# Adafruit_NeoTrellis_M4.net
KiCad netlist of a schematic drawn in EAGLE
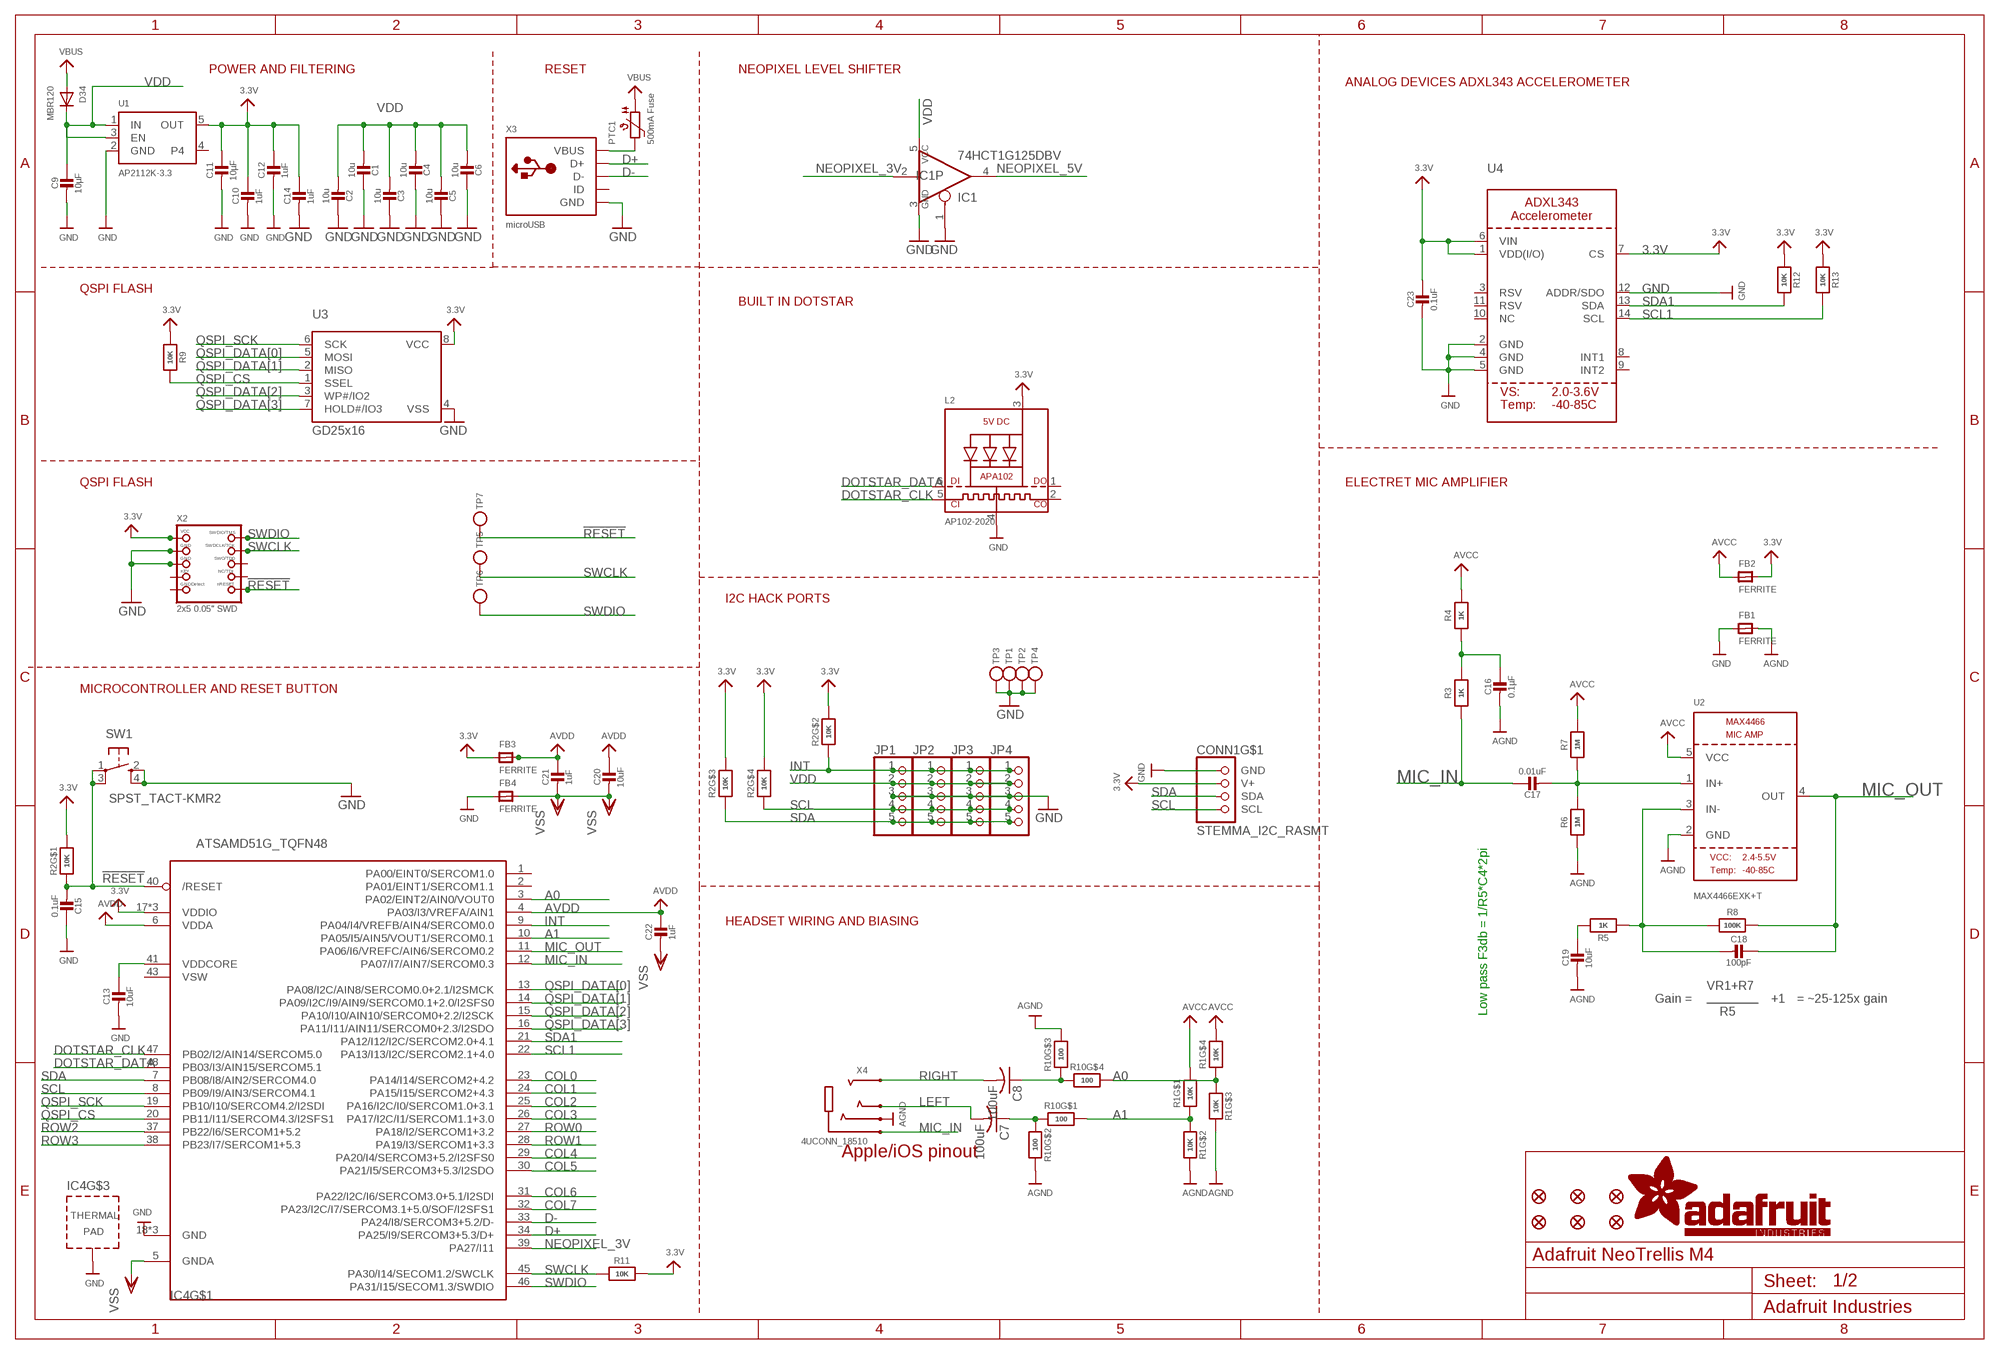
[diagram p0: schematic, sheet 1]
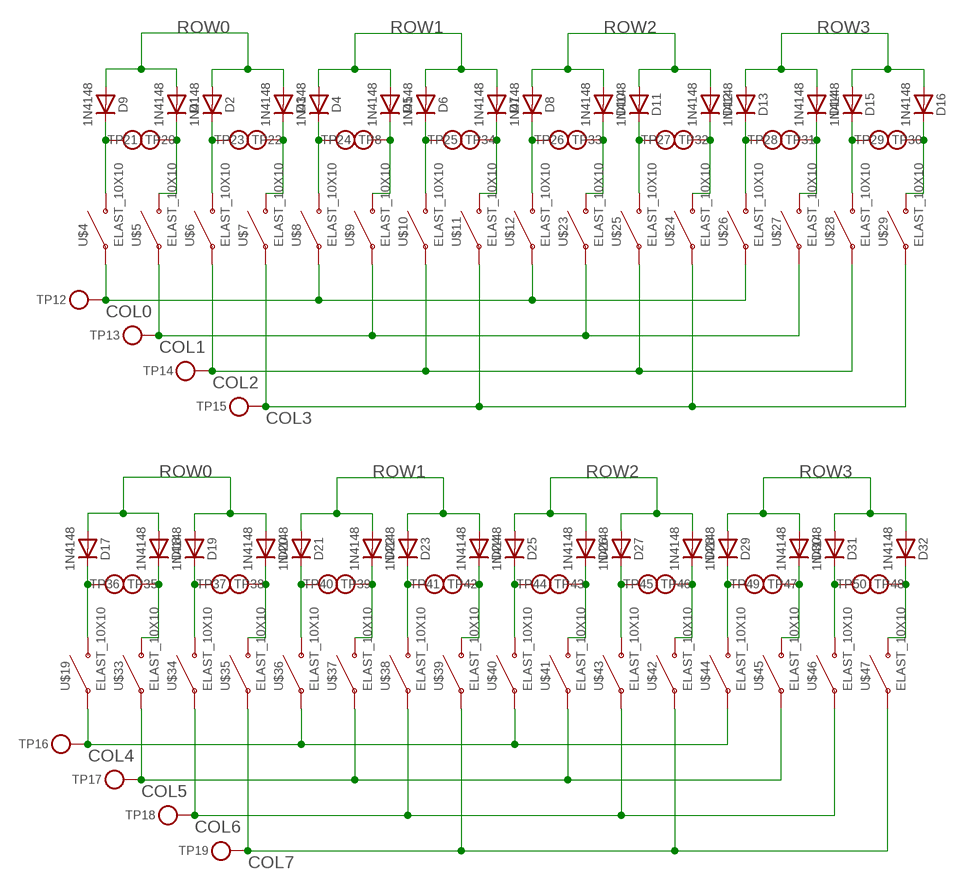
[diagram p1: schematic, sheet 2, part 1 of 2]
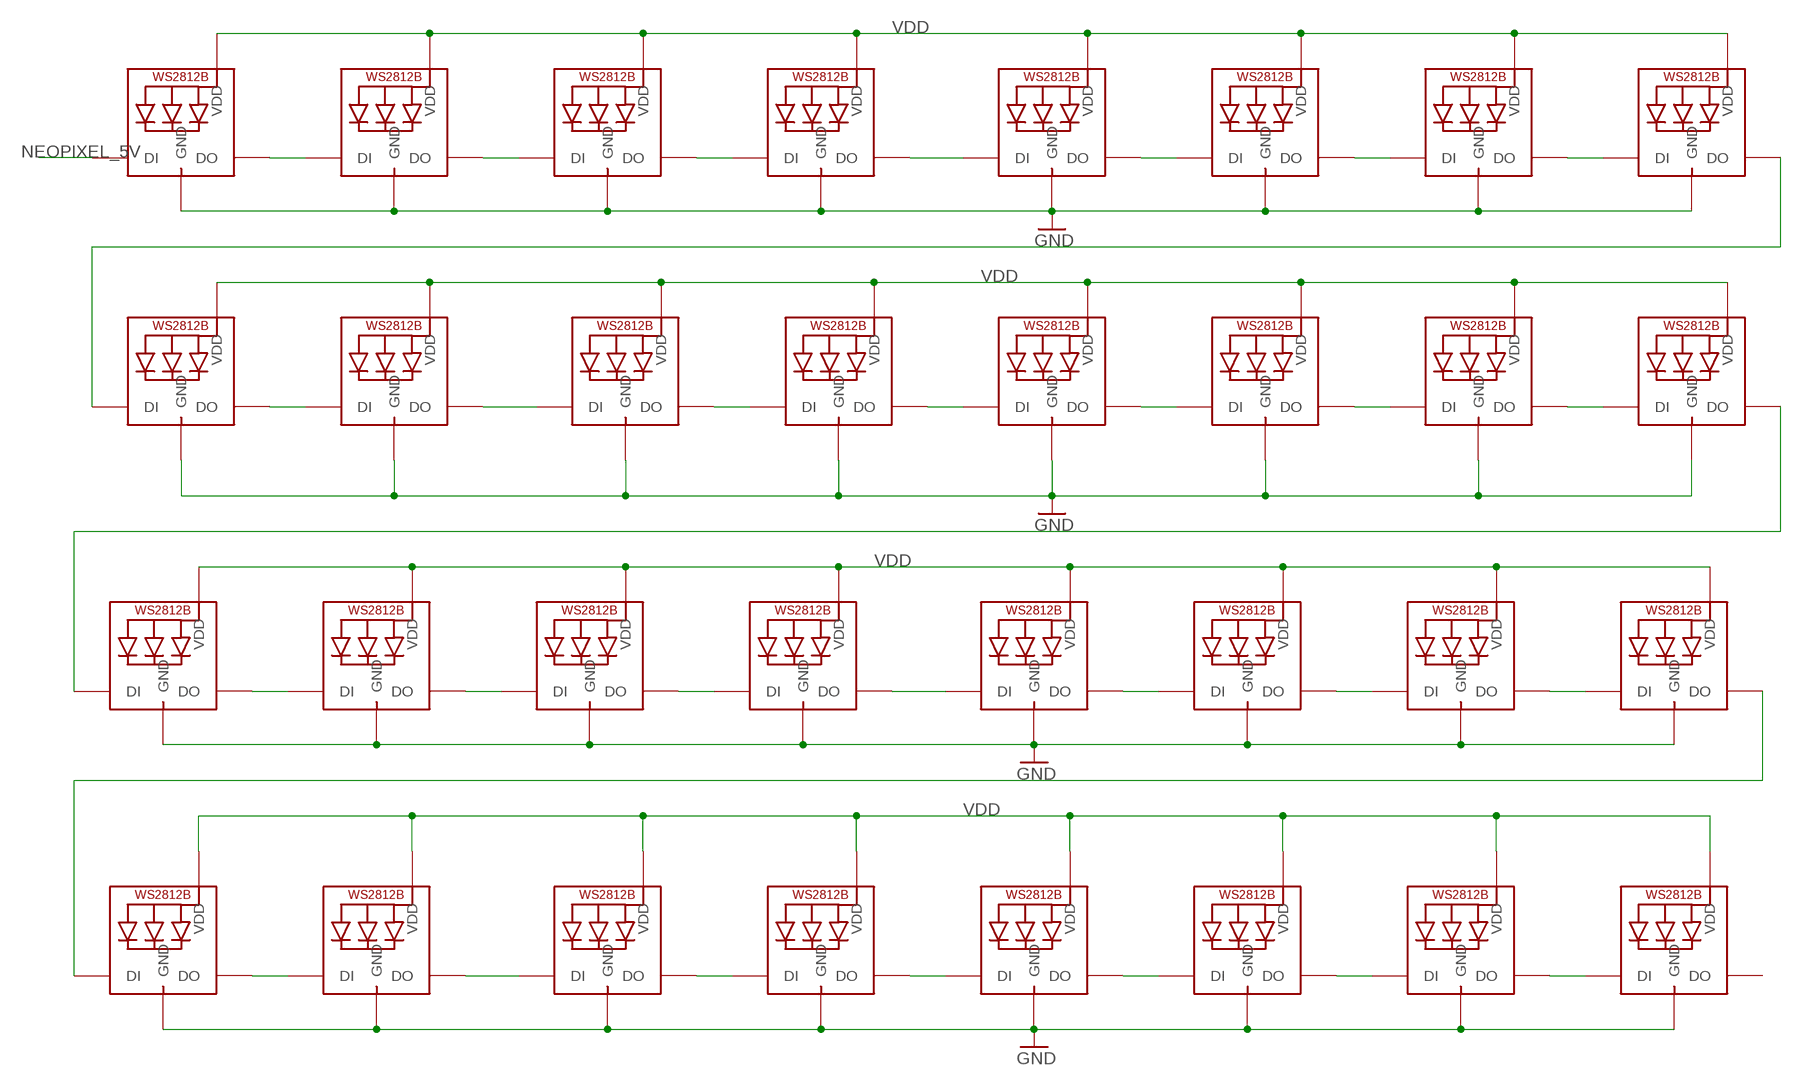
[diagram p2: schematic, sheet 2, part 2 of 2]

(export (version "E")
  (design (tool "Eeschema 10.0.6"))
  (components
    (comp (ref "D1")
      (value "1N4148")
      (footprint "eagle-import:SOD-323")
      (libsource (lib "eagle-import") (part "DIODESOD-323"))
    )
    (comp (ref "D2")
      (value "1N4148")
      (footprint "eagle-import:SOD-323")
      (libsource (lib "eagle-import") (part "DIODESOD-323"))
    )
    (comp (ref "D3")
      (value "1N4148")
      (footprint "eagle-import:SOD-323")
      (libsource (lib "eagle-import") (part "DIODESOD-323"))
    )
    (comp (ref "D4")
      (value "1N4148")
      (footprint "eagle-import:SOD-323")
      (libsource (lib "eagle-import") (part "DIODESOD-323"))
    )
    (comp (ref "D5")
      (value "1N4148")
      (footprint "eagle-import:SOD-323")
      (libsource (lib "eagle-import") (part "DIODESOD-323"))
    )
    (comp (ref "D6")
      (value "1N4148")
      (footprint "eagle-import:SOD-323")
      (libsource (lib "eagle-import") (part "DIODESOD-323"))
    )
    (comp (ref "D7")
      (value "1N4148")
      (footprint "eagle-import:SOD-323")
      (libsource (lib "eagle-import") (part "DIODESOD-323"))
    )
    (comp (ref "D8")
      (value "1N4148")
      (footprint "eagle-import:SOD-323")
      (libsource (lib "eagle-import") (part "DIODESOD-323"))
    )
    (comp (ref "D9")
      (value "1N4148")
      (footprint "eagle-import:SOD-323")
      (libsource (lib "eagle-import") (part "DIODESOD-323"))
    )
    (comp (ref "D10")
      (value "1N4148")
      (footprint "eagle-import:SOD-323")
      (libsource (lib "eagle-import") (part "DIODESOD-323"))
    )
    (comp (ref "D11")
      (value "1N4148")
      (footprint "eagle-import:SOD-323")
      (libsource (lib "eagle-import") (part "DIODESOD-323"))
    )
    (comp (ref "D12")
      (value "1N4148")
      (footprint "eagle-import:SOD-323")
      (libsource (lib "eagle-import") (part "DIODESOD-323"))
    )
    (comp (ref "D13")
      (value "1N4148")
      (footprint "eagle-import:SOD-323")
      (libsource (lib "eagle-import") (part "DIODESOD-323"))
    )
    (comp (ref "D14")
      (value "1N4148")
      (footprint "eagle-import:SOD-323")
      (libsource (lib "eagle-import") (part "DIODESOD-323"))
    )
    (comp (ref "D15")
      (value "1N4148")
      (footprint "eagle-import:SOD-323")
      (libsource (lib "eagle-import") (part "DIODESOD-323"))
    )
    (comp (ref "D16")
      (value "1N4148")
      (footprint "eagle-import:SOD-323")
      (libsource (lib "eagle-import") (part "DIODESOD-323"))
    )
    (comp (ref "D17")
      (value "1N4148")
      (footprint "eagle-import:SOD-323")
      (libsource (lib "eagle-import") (part "DIODESOD-323"))
    )
    (comp (ref "D18")
      (value "1N4148")
      (footprint "eagle-import:SOD-323")
      (libsource (lib "eagle-import") (part "DIODESOD-323"))
    )
    (comp (ref "D19")
      (value "1N4148")
      (footprint "eagle-import:SOD-323")
      (libsource (lib "eagle-import") (part "DIODESOD-323"))
    )
    (comp (ref "D20")
      (value "1N4148")
      (footprint "eagle-import:SOD-323")
      (libsource (lib "eagle-import") (part "DIODESOD-323"))
    )
    (comp (ref "D21")
      (value "1N4148")
      (footprint "eagle-import:SOD-323")
      (libsource (lib "eagle-import") (part "DIODESOD-323"))
    )
    (comp (ref "D22")
      (value "1N4148")
      (footprint "eagle-import:SOD-323")
      (libsource (lib "eagle-import") (part "DIODESOD-323"))
    )
    (comp (ref "D23")
      (value "1N4148")
      (footprint "eagle-import:SOD-323")
      (libsource (lib "eagle-import") (part "DIODESOD-323"))
    )
    (comp (ref "D24")
      (value "1N4148")
      (footprint "eagle-import:SOD-323")
      (libsource (lib "eagle-import") (part "DIODESOD-323"))
    )
    (comp (ref "D25")
      (value "1N4148")
      (footprint "eagle-import:SOD-323")
      (libsource (lib "eagle-import") (part "DIODESOD-323"))
    )
    (comp (ref "D26")
      (value "1N4148")
      (footprint "eagle-import:SOD-323")
      (libsource (lib "eagle-import") (part "DIODESOD-323"))
    )
    (comp (ref "D27")
      (value "1N4148")
      (footprint "eagle-import:SOD-323")
      (libsource (lib "eagle-import") (part "DIODESOD-323"))
    )
    (comp (ref "D28")
      (value "1N4148")
      (footprint "eagle-import:SOD-323")
      (libsource (lib "eagle-import") (part "DIODESOD-323"))
    )
    (comp (ref "D29")
      (value "1N4148")
      (footprint "eagle-import:SOD-323")
      (libsource (lib "eagle-import") (part "DIODESOD-323"))
    )
    (comp (ref "D30")
      (value "1N4148")
      (footprint "eagle-import:SOD-323")
      (libsource (lib "eagle-import") (part "DIODESOD-323"))
    )
    (comp (ref "D31")
      (value "1N4148")
      (footprint "eagle-import:SOD-323")
      (libsource (lib "eagle-import") (part "DIODESOD-323"))
    )
    (comp (ref "D32")
      (value "1N4148")
      (footprint "eagle-import:SOD-323")
      (libsource (lib "eagle-import") (part "DIODESOD-323"))
    )
    (comp (ref "LED1")
      (value "WS2812B3535")
      (footprint "eagle-import:LED3535")
      (libsource (lib "eagle-import") (part "WS2812B3535"))
    )
    (comp (ref "LED2")
      (value "WS2812B3535")
      (footprint "eagle-import:LED3535")
      (libsource (lib "eagle-import") (part "WS2812B3535"))
    )
    (comp (ref "LED3")
      (value "WS2812B3535")
      (footprint "eagle-import:LED3535")
      (libsource (lib "eagle-import") (part "WS2812B3535"))
    )
    (comp (ref "LED4")
      (value "WS2812B3535")
      (footprint "eagle-import:LED3535")
      (libsource (lib "eagle-import") (part "WS2812B3535"))
    )
    (comp (ref "LED5")
      (value "WS2812B3535")
      (footprint "eagle-import:LED3535")
      (libsource (lib "eagle-import") (part "WS2812B3535"))
    )
    (comp (ref "LED6")
      (value "WS2812B3535")
      (footprint "eagle-import:LED3535")
      (libsource (lib "eagle-import") (part "WS2812B3535"))
    )
    (comp (ref "LED7")
      (value "WS2812B3535")
      (footprint "eagle-import:LED3535")
      (libsource (lib "eagle-import") (part "WS2812B3535"))
    )
    (comp (ref "LED8")
      (value "WS2812B3535")
      (footprint "eagle-import:LED3535")
      (libsource (lib "eagle-import") (part "WS2812B3535"))
    )
    (comp (ref "LED9")
      (value "WS2812B3535")
      (footprint "eagle-import:LED3535")
      (libsource (lib "eagle-import") (part "WS2812B3535"))
    )
    (comp (ref "LED10")
      (value "WS2812B3535")
      (footprint "eagle-import:LED3535")
      (libsource (lib "eagle-import") (part "WS2812B3535"))
    )
    (comp (ref "LED11")
      (value "WS2812B3535")
      (footprint "eagle-import:LED3535")
      (libsource (lib "eagle-import") (part "WS2812B3535"))
    )
    (comp (ref "LED12")
      (value "WS2812B3535")
      (footprint "eagle-import:LED3535")
      (libsource (lib "eagle-import") (part "WS2812B3535"))
    )
    (comp (ref "LED13")
      (value "WS2812B3535")
      (footprint "eagle-import:LED3535")
      (libsource (lib "eagle-import") (part "WS2812B3535"))
    )
    (comp (ref "LED14")
      (value "WS2812B3535")
      (footprint "eagle-import:LED3535")
      (libsource (lib "eagle-import") (part "WS2812B3535"))
    )
    (comp (ref "LED15")
      (value "WS2812B3535")
      (footprint "eagle-import:LED3535")
      (libsource (lib "eagle-import") (part "WS2812B3535"))
    )
    (comp (ref "LED16")
      (value "WS2812B3535")
      (footprint "eagle-import:LED3535")
      (libsource (lib "eagle-import") (part "WS2812B3535"))
    )
    (comp (ref "LED17")
      (value "WS2812B3535")
      (footprint "eagle-import:LED3535")
      (libsource (lib "eagle-import") (part "WS2812B3535"))
    )
    (comp (ref "LED18")
      (value "WS2812B3535")
      (footprint "eagle-import:LED3535")
      (libsource (lib "eagle-import") (part "WS2812B3535"))
    )
    (comp (ref "LED19")
      (value "WS2812B3535")
      (footprint "eagle-import:LED3535")
      (libsource (lib "eagle-import") (part "WS2812B3535"))
    )
    (comp (ref "LED20")
      (value "WS2812B3535")
      (footprint "eagle-import:LED3535")
      (libsource (lib "eagle-import") (part "WS2812B3535"))
    )
    (comp (ref "LED21")
      (value "WS2812B3535")
      (footprint "eagle-import:LED3535")
      (libsource (lib "eagle-import") (part "WS2812B3535"))
    )
    (comp (ref "LED22")
      (value "WS2812B3535")
      (footprint "eagle-import:LED3535")
      (libsource (lib "eagle-import") (part "WS2812B3535"))
    )
    (comp (ref "LED23")
      (value "WS2812B3535")
      (footprint "eagle-import:LED3535")
      (libsource (lib "eagle-import") (part "WS2812B3535"))
    )
    (comp (ref "LED24")
      (value "WS2812B3535")
      (footprint "eagle-import:LED3535")
      (libsource (lib "eagle-import") (part "WS2812B3535"))
    )
    (comp (ref "LED25")
      (value "WS2812B3535")
      (footprint "eagle-import:LED3535")
      (libsource (lib "eagle-import") (part "WS2812B3535"))
    )
    (comp (ref "LED26")
      (value "WS2812B3535")
      (footprint "eagle-import:LED3535")
      (libsource (lib "eagle-import") (part "WS2812B3535"))
    )
    (comp (ref "LED27")
      (value "WS2812B3535")
      (footprint "eagle-import:LED3535")
      (libsource (lib "eagle-import") (part "WS2812B3535"))
    )
    (comp (ref "LED28")
      (value "WS2812B3535")
      (footprint "eagle-import:LED3535")
      (libsource (lib "eagle-import") (part "WS2812B3535"))
    )
    (comp (ref "LED29")
      (value "WS2812B3535")
      (footprint "eagle-import:LED3535")
      (libsource (lib "eagle-import") (part "WS2812B3535"))
    )
    (comp (ref "LED30")
      (value "WS2812B3535")
      (footprint "eagle-import:LED3535")
      (libsource (lib "eagle-import") (part "WS2812B3535"))
    )
    (comp (ref "LED31")
      (value "WS2812B3535")
      (footprint "eagle-import:LED3535")
      (libsource (lib "eagle-import") (part "WS2812B3535"))
    )
    (comp (ref "LED32")
      (value "WS2812B3535")
      (footprint "eagle-import:LED3535")
      (libsource (lib "eagle-import") (part "WS2812B3535"))
    )
    (comp (ref "TP8")
      (value "TESTPOINTROUND1.5MM")
      (footprint "eagle-import:TESTPOINT_ROUND_1.5MM")
      (libsource (lib "eagle-import") (part "TESTPOINTROUND1.5MM"))
    )
    (comp (ref "TP12")
      (value "TESTPOINTROUND1.5MM")
      (footprint "eagle-import:TESTPOINT_ROUND_1.5MM")
      (libsource (lib "eagle-import") (part "TESTPOINTROUND1.5MM"))
    )
    (comp (ref "TP13")
      (value "TESTPOINTROUND1.5MM")
      (footprint "eagle-import:TESTPOINT_ROUND_1.5MM")
      (libsource (lib "eagle-import") (part "TESTPOINTROUND1.5MM"))
    )
    (comp (ref "TP14")
      (value "TESTPOINTROUND1.5MM")
      (footprint "eagle-import:TESTPOINT_ROUND_1.5MM")
      (libsource (lib "eagle-import") (part "TESTPOINTROUND1.5MM"))
    )
    (comp (ref "TP15")
      (value "TESTPOINTROUND1.5MM")
      (footprint "eagle-import:TESTPOINT_ROUND_1.5MM")
      (libsource (lib "eagle-import") (part "TESTPOINTROUND1.5MM"))
    )
    (comp (ref "TP16")
      (value "TESTPOINTROUND1.5MM")
      (footprint "eagle-import:TESTPOINT_ROUND_1.5MM")
      (libsource (lib "eagle-import") (part "TESTPOINTROUND1.5MM"))
    )
    (comp (ref "TP17")
      (value "TESTPOINTROUND1.5MM")
      (footprint "eagle-import:TESTPOINT_ROUND_1.5MM")
      (libsource (lib "eagle-import") (part "TESTPOINTROUND1.5MM"))
    )
    (comp (ref "TP18")
      (value "TESTPOINTROUND1.5MM")
      (footprint "eagle-import:TESTPOINT_ROUND_1.5MM")
      (libsource (lib "eagle-import") (part "TESTPOINTROUND1.5MM"))
    )
    (comp (ref "TP19")
      (value "TESTPOINTROUND1.5MM")
      (footprint "eagle-import:TESTPOINT_ROUND_1.5MM")
      (libsource (lib "eagle-import") (part "TESTPOINTROUND1.5MM"))
    )
    (comp (ref "TP20")
      (value "TESTPOINTROUND1.5MM")
      (footprint "eagle-import:TESTPOINT_ROUND_1.5MM")
      (libsource (lib "eagle-import") (part "TESTPOINTROUND1.5MM"))
    )
    (comp (ref "TP21")
      (value "TESTPOINTROUND1.5MM")
      (footprint "eagle-import:TESTPOINT_ROUND_1.5MM")
      (libsource (lib "eagle-import") (part "TESTPOINTROUND1.5MM"))
    )
    (comp (ref "TP22")
      (value "TESTPOINTROUND1.5MM")
      (footprint "eagle-import:TESTPOINT_ROUND_1.5MM")
      (libsource (lib "eagle-import") (part "TESTPOINTROUND1.5MM"))
    )
    (comp (ref "TP23")
      (value "TESTPOINTROUND1.5MM")
      (footprint "eagle-import:TESTPOINT_ROUND_1.5MM")
      (libsource (lib "eagle-import") (part "TESTPOINTROUND1.5MM"))
    )
    (comp (ref "TP24")
      (value "TESTPOINTROUND1.5MM")
      (footprint "eagle-import:TESTPOINT_ROUND_1.5MM")
      (libsource (lib "eagle-import") (part "TESTPOINTROUND1.5MM"))
    )
    (comp (ref "TP25")
      (value "TESTPOINTROUND1.5MM")
      (footprint "eagle-import:TESTPOINT_ROUND_1.5MM")
      (libsource (lib "eagle-import") (part "TESTPOINTROUND1.5MM"))
    )
    (comp (ref "TP26")
      (value "TESTPOINTROUND1.5MM")
      (footprint "eagle-import:TESTPOINT_ROUND_1.5MM")
      (libsource (lib "eagle-import") (part "TESTPOINTROUND1.5MM"))
    )
    (comp (ref "TP27")
      (value "TESTPOINTROUND1.5MM")
      (footprint "eagle-import:TESTPOINT_ROUND_1.5MM")
      (libsource (lib "eagle-import") (part "TESTPOINTROUND1.5MM"))
    )
    (comp (ref "TP28")
      (value "TESTPOINTROUND1.5MM")
      (footprint "eagle-import:TESTPOINT_ROUND_1.5MM")
      (libsource (lib "eagle-import") (part "TESTPOINTROUND1.5MM"))
    )
    (comp (ref "TP29")
      (value "TESTPOINTROUND1.5MM")
      (footprint "eagle-import:TESTPOINT_ROUND_1.5MM")
      (libsource (lib "eagle-import") (part "TESTPOINTROUND1.5MM"))
    )
    (comp (ref "TP30")
      (value "TESTPOINTROUND1.5MM")
      (footprint "eagle-import:TESTPOINT_ROUND_1.5MM")
      (libsource (lib "eagle-import") (part "TESTPOINTROUND1.5MM"))
    )
    (comp (ref "TP31")
      (value "TESTPOINTROUND1.5MM")
      (footprint "eagle-import:TESTPOINT_ROUND_1.5MM")
      (libsource (lib "eagle-import") (part "TESTPOINTROUND1.5MM"))
    )
    (comp (ref "TP32")
      (value "TESTPOINTROUND1.5MM")
      (footprint "eagle-import:TESTPOINT_ROUND_1.5MM")
      (libsource (lib "eagle-import") (part "TESTPOINTROUND1.5MM"))
    )
    (comp (ref "TP33")
      (value "TESTPOINTROUND1.5MM")
      (footprint "eagle-import:TESTPOINT_ROUND_1.5MM")
      (libsource (lib "eagle-import") (part "TESTPOINTROUND1.5MM"))
    )
    (comp (ref "TP34")
      (value "TESTPOINTROUND1.5MM")
      (footprint "eagle-import:TESTPOINT_ROUND_1.5MM")
      (libsource (lib "eagle-import") (part "TESTPOINTROUND1.5MM"))
    )
    (comp (ref "TP35")
      (value "TESTPOINTROUND1.5MM")
      (footprint "eagle-import:TESTPOINT_ROUND_1.5MM")
      (libsource (lib "eagle-import") (part "TESTPOINTROUND1.5MM"))
    )
    (comp (ref "TP36")
      (value "TESTPOINTROUND1.5MM")
      (footprint "eagle-import:TESTPOINT_ROUND_1.5MM")
      (libsource (lib "eagle-import") (part "TESTPOINTROUND1.5MM"))
    )
    (comp (ref "TP37")
      (value "TESTPOINTROUND1.5MM")
      (footprint "eagle-import:TESTPOINT_ROUND_1.5MM")
      (libsource (lib "eagle-import") (part "TESTPOINTROUND1.5MM"))
    )
    (comp (ref "TP38")
      (value "TESTPOINTROUND1.5MM")
      (footprint "eagle-import:TESTPOINT_ROUND_1.5MM")
      (libsource (lib "eagle-import") (part "TESTPOINTROUND1.5MM"))
    )
    (comp (ref "TP39")
      (value "TESTPOINTROUND1.5MM")
      (footprint "eagle-import:TESTPOINT_ROUND_1.5MM")
      (libsource (lib "eagle-import") (part "TESTPOINTROUND1.5MM"))
    )
    (comp (ref "TP40")
      (value "TESTPOINTROUND1.5MM")
      (footprint "eagle-import:TESTPOINT_ROUND_1.5MM")
      (libsource (lib "eagle-import") (part "TESTPOINTROUND1.5MM"))
    )
    (comp (ref "TP41")
      (value "TESTPOINTROUND1.5MM")
      (footprint "eagle-import:TESTPOINT_ROUND_1.5MM")
      (libsource (lib "eagle-import") (part "TESTPOINTROUND1.5MM"))
    )
    (comp (ref "TP42")
      (value "TESTPOINTROUND1.5MM")
      (footprint "eagle-import:TESTPOINT_ROUND_1.5MM")
      (libsource (lib "eagle-import") (part "TESTPOINTROUND1.5MM"))
    )
    (comp (ref "TP43")
      (value "TESTPOINTROUND1.5MM")
      (footprint "eagle-import:TESTPOINT_ROUND_1.5MM")
      (libsource (lib "eagle-import") (part "TESTPOINTROUND1.5MM"))
    )
    (comp (ref "TP44")
      (value "TESTPOINTROUND1.5MM")
      (footprint "eagle-import:TESTPOINT_ROUND_1.5MM")
      (libsource (lib "eagle-import") (part "TESTPOINTROUND1.5MM"))
    )
    (comp (ref "TP45")
      (value "TESTPOINTROUND1.5MM")
      (footprint "eagle-import:TESTPOINT_ROUND_1.5MM")
      (libsource (lib "eagle-import") (part "TESTPOINTROUND1.5MM"))
    )
    (comp (ref "TP46")
      (value "TESTPOINTROUND1.5MM")
      (footprint "eagle-import:TESTPOINT_ROUND_1.5MM")
      (libsource (lib "eagle-import") (part "TESTPOINTROUND1.5MM"))
    )
    (comp (ref "TP47")
      (value "TESTPOINTROUND1.5MM")
      (footprint "eagle-import:TESTPOINT_ROUND_1.5MM")
      (libsource (lib "eagle-import") (part "TESTPOINTROUND1.5MM"))
    )
    (comp (ref "TP48")
      (value "TESTPOINTROUND1.5MM")
      (footprint "eagle-import:TESTPOINT_ROUND_1.5MM")
      (libsource (lib "eagle-import") (part "TESTPOINTROUND1.5MM"))
    )
    (comp (ref "TP49")
      (value "TESTPOINTROUND1.5MM")
      (footprint "eagle-import:TESTPOINT_ROUND_1.5MM")
      (libsource (lib "eagle-import") (part "TESTPOINTROUND1.5MM"))
    )
    (comp (ref "TP50")
      (value "TESTPOINTROUND1.5MM")
      (footprint "eagle-import:TESTPOINT_ROUND_1.5MM")
      (libsource (lib "eagle-import") (part "TESTPOINTROUND1.5MM"))
    )
    (comp (ref "U$4")
      (value "ELAST_10X10")
      (footprint "eagle-import:ELAST_PAD_SQUARE_10MM_4X4WIDE")
      (libsource (lib "eagle-import") (part "ELAST_10X10"))
    )
    (comp (ref "U$5")
      (value "ELAST_10X10")
      (footprint "eagle-import:ELAST_PAD_SQUARE_10MM_4X4WIDE")
      (libsource (lib "eagle-import") (part "ELAST_10X10"))
    )
    (comp (ref "U$6")
      (value "ELAST_10X10")
      (footprint "eagle-import:ELAST_PAD_SQUARE_10MM_4X4WIDE")
      (libsource (lib "eagle-import") (part "ELAST_10X10"))
    )
    (comp (ref "U$7")
      (value "ELAST_10X10")
      (footprint "eagle-import:ELAST_PAD_SQUARE_10MM_4X4WIDE")
      (libsource (lib "eagle-import") (part "ELAST_10X10"))
    )
    (comp (ref "U$8")
      (value "ELAST_10X10")
      (footprint "eagle-import:ELAST_PAD_SQUARE_10MM_4X4WIDE")
      (libsource (lib "eagle-import") (part "ELAST_10X10"))
    )
    (comp (ref "U$9")
      (value "ELAST_10X10")
      (footprint "eagle-import:ELAST_PAD_SQUARE_10MM_4X4WIDE")
      (libsource (lib "eagle-import") (part "ELAST_10X10"))
    )
    (comp (ref "U$10")
      (value "ELAST_10X10")
      (footprint "eagle-import:ELAST_PAD_SQUARE_10MM_4X4WIDE")
      (libsource (lib "eagle-import") (part "ELAST_10X10"))
    )
    (comp (ref "U$11")
      (value "ELAST_10X10")
      (footprint "eagle-import:ELAST_PAD_SQUARE_10MM_4X4WIDE")
      (libsource (lib "eagle-import") (part "ELAST_10X10"))
    )
    (comp (ref "U$12")
      (value "ELAST_10X10")
      (footprint "eagle-import:ELAST_PAD_SQUARE_10MM_4X4WIDE")
      (libsource (lib "eagle-import") (part "ELAST_10X10"))
    )
    (comp (ref "U$19")
      (value "ELAST_10X10")
      (footprint "eagle-import:ELAST_PAD_SQUARE_10MM_4X4WIDE")
      (libsource (lib "eagle-import") (part "ELAST_10X10"))
    )
    (comp (ref "U$23")
      (value "ELAST_10X10")
      (footprint "eagle-import:ELAST_PAD_SQUARE_10MM_4X4WIDE")
      (libsource (lib "eagle-import") (part "ELAST_10X10"))
    )
    (comp (ref "U$24")
      (value "ELAST_10X10")
      (footprint "eagle-import:ELAST_PAD_SQUARE_10MM_4X4WIDE")
      (libsource (lib "eagle-import") (part "ELAST_10X10"))
    )
    (comp (ref "U$25")
      (value "ELAST_10X10")
      (footprint "eagle-import:ELAST_PAD_SQUARE_10MM_4X4WIDE")
      (libsource (lib "eagle-import") (part "ELAST_10X10"))
    )
    (comp (ref "U$26")
      (value "ELAST_10X10")
      (footprint "eagle-import:ELAST_PAD_SQUARE_10MM_4X4WIDE")
      (libsource (lib "eagle-import") (part "ELAST_10X10"))
    )
    (comp (ref "U$27")
      (value "ELAST_10X10")
      (footprint "eagle-import:ELAST_PAD_SQUARE_10MM_4X4WIDE")
      (libsource (lib "eagle-import") (part "ELAST_10X10"))
    )
    (comp (ref "U$28")
      (value "ELAST_10X10")
      (footprint "eagle-import:ELAST_PAD_SQUARE_10MM_4X4WIDE")
      (libsource (lib "eagle-import") (part "ELAST_10X10"))
    )
    (comp (ref "U$29")
      (value "ELAST_10X10")
      (footprint "eagle-import:ELAST_PAD_SQUARE_10MM_4X4WIDE")
      (libsource (lib "eagle-import") (part "ELAST_10X10"))
    )
    (comp (ref "U$33")
      (value "ELAST_10X10")
      (footprint "eagle-import:ELAST_PAD_SQUARE_10MM_4X4WIDE")
      (libsource (lib "eagle-import") (part "ELAST_10X10"))
    )
    (comp (ref "U$34")
      (value "ELAST_10X10")
      (footprint "eagle-import:ELAST_PAD_SQUARE_10MM_4X4WIDE")
      (libsource (lib "eagle-import") (part "ELAST_10X10"))
    )
    (comp (ref "U$35")
      (value "ELAST_10X10")
      (footprint "eagle-import:ELAST_PAD_SQUARE_10MM_4X4WIDE")
      (libsource (lib "eagle-import") (part "ELAST_10X10"))
    )
    (comp (ref "U$36")
      (value "ELAST_10X10")
      (footprint "eagle-import:ELAST_PAD_SQUARE_10MM_4X4WIDE")
      (libsource (lib "eagle-import") (part "ELAST_10X10"))
    )
    (comp (ref "U$37")
      (value "ELAST_10X10")
      (footprint "eagle-import:ELAST_PAD_SQUARE_10MM_4X4WIDE")
      (libsource (lib "eagle-import") (part "ELAST_10X10"))
    )
    (comp (ref "U$38")
      (value "ELAST_10X10")
      (footprint "eagle-import:ELAST_PAD_SQUARE_10MM_4X4WIDE")
      (libsource (lib "eagle-import") (part "ELAST_10X10"))
    )
    (comp (ref "U$39")
      (value "ELAST_10X10")
      (footprint "eagle-import:ELAST_PAD_SQUARE_10MM_4X4WIDE")
      (libsource (lib "eagle-import") (part "ELAST_10X10"))
    )
    (comp (ref "U$40")
      (value "ELAST_10X10")
      (footprint "eagle-import:ELAST_PAD_SQUARE_10MM_4X4WIDE")
      (libsource (lib "eagle-import") (part "ELAST_10X10"))
    )
    (comp (ref "U$41")
      (value "ELAST_10X10")
      (footprint "eagle-import:ELAST_PAD_SQUARE_10MM_4X4WIDE")
      (libsource (lib "eagle-import") (part "ELAST_10X10"))
    )
    (comp (ref "U$42")
      (value "ELAST_10X10")
      (footprint "eagle-import:ELAST_PAD_SQUARE_10MM_4X4WIDE")
      (libsource (lib "eagle-import") (part "ELAST_10X10"))
    )
    (comp (ref "U$43")
      (value "ELAST_10X10")
      (footprint "eagle-import:ELAST_PAD_SQUARE_10MM_4X4WIDE")
      (libsource (lib "eagle-import") (part "ELAST_10X10"))
    )
    (comp (ref "U$44")
      (value "ELAST_10X10")
      (footprint "eagle-import:ELAST_PAD_SQUARE_10MM_4X4WIDE")
      (libsource (lib "eagle-import") (part "ELAST_10X10"))
    )
    (comp (ref "U$45")
      (value "ELAST_10X10")
      (footprint "eagle-import:ELAST_PAD_SQUARE_10MM_4X4WIDE")
      (libsource (lib "eagle-import") (part "ELAST_10X10"))
    )
    (comp (ref "U$46")
      (value "ELAST_10X10")
      (footprint "eagle-import:ELAST_PAD_SQUARE_10MM_4X4WIDE")
      (libsource (lib "eagle-import") (part "ELAST_10X10"))
    )
    (comp (ref "U$47")
      (value "ELAST_10X10")
      (footprint "eagle-import:ELAST_PAD_SQUARE_10MM_4X4WIDE")
      (libsource (lib "eagle-import") (part "ELAST_10X10"))
    )
    (comp (ref "C1")
      (value "10u")
      (footprint "eagle-import:0805-NO")
      (libsource (lib "eagle-import") (part "CAP_CERAMIC0805-NOOUTLINE"))
    )
    (comp (ref "C2")
      (value "10u")
      (footprint "eagle-import:0805-NO")
      (libsource (lib "eagle-import") (part "CAP_CERAMIC0805-NOOUTLINE"))
    )
    (comp (ref "C3")
      (value "10u")
      (footprint "eagle-import:0805-NO")
      (libsource (lib "eagle-import") (part "CAP_CERAMIC0805-NOOUTLINE"))
    )
    (comp (ref "C4")
      (value "10u")
      (footprint "eagle-import:0805-NO")
      (libsource (lib "eagle-import") (part "CAP_CERAMIC0805-NOOUTLINE"))
    )
    (comp (ref "C5")
      (value "10u")
      (footprint "eagle-import:0805-NO")
      (libsource (lib "eagle-import") (part "CAP_CERAMIC0805-NOOUTLINE"))
    )
    (comp (ref "C6")
      (value "10u")
      (footprint "eagle-import:0805-NO")
      (libsource (lib "eagle-import") (part "CAP_CERAMIC0805-NOOUTLINE"))
    )
    (comp (ref "C7")
      (value "100uF")
      (footprint "eagle-import:C1210")
      (libsource (lib "eagle-import") (part "C-USC1210"))
    )
    (comp (ref "C8")
      (value "100uF")
      (footprint "eagle-import:C1210")
      (libsource (lib "eagle-import") (part "C-USC1210"))
    )
    (comp (ref "C9")
      (value "10µF")
      (footprint "eagle-import:0805-NO")
      (libsource (lib "eagle-import") (part "CAP_CERAMIC0805-NOOUTLINE"))
    )
    (comp (ref "C10")
      (value "1uF")
      (footprint "eagle-import:0603-NO")
      (libsource (lib "eagle-import") (part "CAP_CERAMIC0603_NO"))
    )
    (comp (ref "C11")
      (value "10µF")
      (footprint "eagle-import:0805-NO")
      (libsource (lib "eagle-import") (part "CAP_CERAMIC0805-NOOUTLINE"))
    )
    (comp (ref "C12")
      (value "1uF")
      (footprint "eagle-import:0603-NO")
      (libsource (lib "eagle-import") (part "CAP_CERAMIC0603_NO"))
    )
    (comp (ref "C13")
      (value "10uF")
      (footprint "eagle-import:0805-NO")
      (libsource (lib "eagle-import") (part "CAP_CERAMIC0805-NOOUTLINE"))
    )
    (comp (ref "C14")
      (value "1uF")
      (footprint "eagle-import:0603-NO")
      (libsource (lib "eagle-import") (part "CAP_CERAMIC0603_NO"))
    )
    (comp (ref "C15")
      (value "0.1uF")
      (footprint "eagle-import:0603-NO")
      (libsource (lib "eagle-import") (part "CAP_CERAMIC0603_NO"))
    )
    (comp (ref "C16")
      (value "0.1µF")
      (footprint "eagle-import:0603-NO")
      (libsource (lib "eagle-import") (part "CAP_CERAMIC0603_NO"))
    )
    (comp (ref "C17")
      (value "0.01uF")
      (footprint "eagle-import:0603-NO")
      (libsource (lib "eagle-import") (part "CAP_CERAMIC0603_NO"))
    )
    (comp (ref "C18")
      (value "100pF")
      (footprint "eagle-import:0603-NO")
      (libsource (lib "eagle-import") (part "CAP_CERAMIC0603_NO"))
    )
    (comp (ref "C19")
      (value "10uF")
      (footprint "eagle-import:0805-NO")
      (libsource (lib "eagle-import") (part "CAP_CERAMIC0805-NOOUTLINE"))
    )
    (comp (ref "C20")
      (value "10uF")
      (footprint "eagle-import:0805-NO")
      (libsource (lib "eagle-import") (part "CAP_CERAMIC0805-NOOUTLINE"))
    )
    (comp (ref "C21")
      (value "1uF")
      (footprint "eagle-import:0603-NO")
      (libsource (lib "eagle-import") (part "CAP_CERAMIC0603_NO"))
    )
    (comp (ref "C22")
      (value "1uF")
      (footprint "eagle-import:0603-NO")
      (libsource (lib "eagle-import") (part "CAP_CERAMIC0603_NO"))
    )
    (comp (ref "C23")
      (value "0.1uF")
      (footprint "eagle-import:0603-NO")
      (libsource (lib "eagle-import") (part "CAP_CERAMIC0603_NO"))
    )
    (comp (ref "CONN1")
      (value "STEMMA_I2C_RASMT")
      (footprint "eagle-import:JSTPH4")
      (libsource (lib "eagle-import") (part "STEMMA_I2C_RASMT"))
    )
    (comp (ref "D34")
      (value "MBR120")
      (footprint "eagle-import:SOD-123FL")
      (libsource (lib "eagle-import") (part "DIODE_SOD-123FL"))
    )
    (comp (ref "FB1")
      (value "FERRITE")
      (footprint "eagle-import:0805")
      (libsource (lib "eagle-import") (part "FERRITE0805"))
    )
    (comp (ref "FB2")
      (value "FERRITE")
      (footprint "eagle-import:0805")
      (libsource (lib "eagle-import") (part "FERRITE0805"))
    )
    (comp (ref "FB3")
      (value "FERRITE")
      (footprint "eagle-import:0805-NO")
      (libsource (lib "eagle-import") (part "FERRITE-0805NO"))
    )
    (comp (ref "FB4")
      (value "FERRITE")
      (footprint "eagle-import:0805-NO")
      (libsource (lib "eagle-import") (part "FERRITE-0805NO"))
    )
    (comp (ref "FID1")
      (value "FIDUCIAL_1MM")
      (footprint "eagle-import:FIDUCIAL_1MM")
      (libsource (lib "eagle-import") (part "FIDUCIAL_1MM"))
    )
    (comp (ref "FID2")
      (value "FIDUCIAL_1MM")
      (footprint "eagle-import:FIDUCIAL_1MM")
      (libsource (lib "eagle-import") (part "FIDUCIAL_1MM"))
    )
    (comp (ref "FID3")
      (value "FIDUCIAL_1MM")
      (footprint "eagle-import:FIDUCIAL_1MM")
      (libsource (lib "eagle-import") (part "FIDUCIAL_1MM"))
    )
    (comp (ref "FID4")
      (value "FIDUCIAL_1MM")
      (footprint "eagle-import:FIDUCIAL_1MM")
      (libsource (lib "eagle-import") (part "FIDUCIAL_1MM"))
    )
    (comp (ref "FID5")
      (value "FIDUCIAL_1MM")
      (footprint "eagle-import:FIDUCIAL_1MM")
      (libsource (lib "eagle-import") (part "FIDUCIAL_1MM"))
    )
    (comp (ref "FID6")
      (value "FIDUCIAL_1MM")
      (footprint "eagle-import:FIDUCIAL_1MM")
      (libsource (lib "eagle-import") (part "FIDUCIAL_1MM"))
    )
    (comp (ref "IC1")
      (value "74HCT1G125DBV")
      (footprint "eagle-import:SOT23-5")
      (libsource (lib "eagle-import") (part "741G125DBVAHC"))
    )
    (comp (ref "IC4")
      (value "ATSAMD51G_TQFN48")
      (footprint "eagle-import:TQFN48_7MM")
      (libsource (lib "eagle-import") (part "ATSAMD51G_TQFN48"))
    )
    (comp (ref "JP1")
      (value "HEADER-1X5EDGESMT")
      (footprint "eagle-import:5P_EDGECONNECT")
      (libsource (lib "eagle-import") (part "HEADER-1X5EDGESMT"))
    )
    (comp (ref "JP2")
      (value "HEADER-1X5EDGESMT")
      (footprint "eagle-import:5P_EDGECONNECT")
      (libsource (lib "eagle-import") (part "HEADER-1X5EDGESMT"))
    )
    (comp (ref "JP3")
      (value "HEADER-1X5EDGESMT")
      (footprint "eagle-import:5P_EDGECONNECT")
      (libsource (lib "eagle-import") (part "HEADER-1X5EDGESMT"))
    )
    (comp (ref "JP4")
      (value "HEADER-1X5EDGESMT")
      (footprint "eagle-import:5P_EDGECONNECT")
      (libsource (lib "eagle-import") (part "HEADER-1X5EDGESMT"))
    )
    (comp (ref "L2")
      (value "AP102-2020")
      (footprint "eagle-import:APA102_2020")
      (libsource (lib "eagle-import") (part "APA1022020"))
    )
    (comp (ref "PTC1")
      (value "500mA Fuse")
      (footprint "eagle-import:1206")
      (libsource (lib "eagle-import") (part "PTC1206"))
    )
    (comp (ref "R1")
      (value "10K")
      (footprint "eagle-import:RESPACK_4X0603")
      (libsource (lib "eagle-import") (part "RESISTOR_4PACK"))
    )
    (comp (ref "R2")
      (value "10K")
      (footprint "eagle-import:RESPACK_4X0603")
      (libsource (lib "eagle-import") (part "RESISTOR_4PACK"))
    )
    (comp (ref "R3")
      (value "1K")
      (footprint "eagle-import:0603-NO")
      (libsource (lib "eagle-import") (part "RESISTOR_0603_NOOUT"))
    )
    (comp (ref "R4")
      (value "1K")
      (footprint "eagle-import:0603-NO")
      (libsource (lib "eagle-import") (part "RESISTOR_0603_NOOUT"))
    )
    (comp (ref "R5")
      (value "1K")
      (footprint "eagle-import:0603-NO")
      (libsource (lib "eagle-import") (part "RESISTOR_0603_NOOUT"))
    )
    (comp (ref "R6")
      (value "1M")
      (footprint "eagle-import:0603-NO")
      (libsource (lib "eagle-import") (part "RESISTOR_0603_NOOUT"))
    )
    (comp (ref "R7")
      (value "1M")
      (footprint "eagle-import:0603-NO")
      (libsource (lib "eagle-import") (part "RESISTOR_0603_NOOUT"))
    )
    (comp (ref "R8")
      (value "100K")
      (footprint "eagle-import:0603-NO")
      (libsource (lib "eagle-import") (part "RESISTOR_0603_NOOUT"))
    )
    (comp (ref "R9")
      (value "10K")
      (footprint "eagle-import:0603-NO")
      (libsource (lib "eagle-import") (part "RESISTOR_0603_NOOUT"))
    )
    (comp (ref "R10")
      (value "100")
      (footprint "eagle-import:RESPACK_4X0603")
      (libsource (lib "eagle-import") (part "RESISTOR_4PACK"))
    )
    (comp (ref "R11")
      (value "10K")
      (footprint "eagle-import:0603-NO")
      (libsource (lib "eagle-import") (part "RESISTOR_0603_NOOUT"))
    )
    (comp (ref "R12")
      (value "10K")
      (footprint "eagle-import:0603-NO")
      (libsource (lib "eagle-import") (part "RESISTOR_0603_NOOUT"))
    )
    (comp (ref "R13")
      (value "10K")
      (footprint "eagle-import:0603-NO")
      (libsource (lib "eagle-import") (part "RESISTOR_0603_NOOUT"))
    )
    (comp (ref "SW1")
      (value "SPST_TACT-KMR2")
      (footprint "eagle-import:KMR2")
      (libsource (lib "eagle-import") (part "SPST_TACT-KMR2"))
    )
    (comp (ref "TP1")
      (value "TESTPOINT")
      (footprint "eagle-import:TESTPOINT_SMT")
      (libsource (lib "eagle-import") (part "TESTPOINT"))
    )
    (comp (ref "TP2")
      (value "TESTPOINT")
      (footprint "eagle-import:TESTPOINT_SMT")
      (libsource (lib "eagle-import") (part "TESTPOINT"))
    )
    (comp (ref "TP3")
      (value "TESTPOINT")
      (footprint "eagle-import:TESTPOINT_SMT")
      (libsource (lib "eagle-import") (part "TESTPOINT"))
    )
    (comp (ref "TP4")
      (value "TESTPOINT")
      (footprint "eagle-import:TESTPOINT_SMT")
      (libsource (lib "eagle-import") (part "TESTPOINT"))
    )
    (comp (ref "TP5")
      (value "TESTPOINTROUND2MM")
      (footprint "eagle-import:TESTPOINT_ROUND_2MM")
      (libsource (lib "eagle-import") (part "TESTPOINTROUND2MM"))
    )
    (comp (ref "TP6")
      (value "TESTPOINTROUND2MM")
      (footprint "eagle-import:TESTPOINT_ROUND_2MM")
      (libsource (lib "eagle-import") (part "TESTPOINTROUND2MM"))
    )
    (comp (ref "TP7")
      (value "TESTPOINTROUND1.5MM")
      (footprint "eagle-import:TESTPOINT_ROUND_1.5MM")
      (libsource (lib "eagle-import") (part "TESTPOINTROUND1.5MM"))
    )
    (comp (ref "U1")
      (value "AP2112K-3.3")
      (footprint "eagle-import:SOT23-5")
      (libsource (lib "eagle-import") (part "VREG_SOT23-5"))
    )
    (comp (ref "U2")
      (value "MAX4466EXK+T")
      (footprint "eagle-import:SC70-5")
      (libsource (lib "eagle-import") (part "AUDIOAMP_MAX4466"))
    )
    (comp (ref "U3")
      (value "GD25x16")
      (footprint "eagle-import:SOIC8_208MIL")
      (libsource (lib "eagle-import") (part "SPIFLASH_8PIN208MIL"))
    )
    (comp (ref "U4")
      (value "ACCEL_ADXL343")
      (footprint "eagle-import:LGA14")
      (libsource (lib "eagle-import") (part "ACCEL_ADXL343"))
    )
    (comp (ref "X2")
      (value "2x5 0.05\" SWD")
      (footprint "eagle-import:2X05_1.27MM_BOX_POSTS")
      (libsource (lib "eagle-import") (part "JTAG-CORTEXBOXPOSTS"))
    )
    (comp (ref "X3")
      (value "microUSB")
      (footprint "eagle-import:4UCONN_20329_NARROW")
      (libsource (lib "eagle-import") (part "USB_MICRO_NARROW"))
    )
    (comp (ref "X4")
      (value "4UCONN_18510")
      (footprint "eagle-import:4UCONN_18510")
      (libsource (lib "eagle-import") (part "AUDIO_3.5MMJACK_4POL"))
    )
  )
  (nets
    (net (code "1") (name "3.3V") (class "Default")
      (node (ref "C10") (pin "1") (pinfunction "1_1") (pintype "passive"))
      (node (ref "C11") (pin "1") (pinfunction "1_1") (pintype "passive"))
      (node (ref "C12") (pin "1") (pinfunction "1_1") (pintype "passive"))
      (node (ref "C14") (pin "1") (pinfunction "1_1") (pintype "passive"))
      (node (ref "C23") (pin "1") (pinfunction "1_1") (pintype "passive"))
      (node (ref "CONN1") (pin "2") (pinfunction "V+_2") (pintype "passive"))
      (node (ref "FB2") (pin "2") (pinfunction "P$2_2") (pintype "passive"))
      (node (ref "FB3") (pin "1") (pinfunction "P$1_1") (pintype "passive"))
      (node (ref "IC4") (pin "17") (pinfunction "VDDIO_17") (pintype "power_in"))
      (node (ref "IC4") (pin "36") (pinfunction "VDDIO_36") (pintype "power_in"))
      (node (ref "IC4") (pin "44") (pinfunction "VDDIO_44") (pintype "power_in"))
      (node (ref "L2") (pin "3") (pinfunction "VDD_3") (pintype "power_in"))
      (node (ref "R11") (pin "2") (pinfunction "2_2") (pintype "passive"))
      (node (ref "R12") (pin "1") (pinfunction "1_1") (pintype "passive"))
      (node (ref "R13") (pin "1") (pinfunction "1_1") (pintype "passive"))
      (node (ref "R2") (pin "5") (pinfunction "2_5") (pintype "passive"))
      (node (ref "R2") (pin "6") (pinfunction "2_6") (pintype "passive"))
      (node (ref "R2") (pin "7") (pinfunction "2_7") (pintype "passive"))
      (node (ref "R2") (pin "8") (pinfunction "2_8") (pintype "passive"))
      (node (ref "R9") (pin "1") (pinfunction "1_1") (pintype "passive"))
      (node (ref "U1") (pin "5") (pinfunction "OUT_5") (pintype "power_in"))
      (node (ref "U3") (pin "8") (pinfunction "VCC_8") (pintype "bidirectional"))
      (node (ref "U4") (pin "1") (pinfunction "VDD(I/O)_1") (pintype "bidirectional"))
      (node (ref "U4") (pin "6") (pinfunction "VIN_6") (pintype "bidirectional"))
      (node (ref "U4") (pin "7") (pinfunction "CS_7") (pintype "bidirectional"))
      (node (ref "X2") (pin "1") (pinfunction "VCC_1") (pintype "power_in"))
    )
    (net (code "2") (name "A0") (class "Default")
      (node (ref "IC4") (pin "3") (pinfunction "PA02/EINT2/AIN0/VOUT0_3") (pintype "bidirectional"))
      (node (ref "R1") (pin "3") (pinfunction "1_3") (pintype "passive"))
      (node (ref "R1") (pin "4") (pinfunction "1_4") (pintype "passive"))
      (node (ref "R10") (pin "5") (pinfunction "2_5") (pintype "passive"))
    )
    (net (code "3") (name "A1") (class "Default")
      (node (ref "IC4") (pin "10") (pinfunction "PA05/I5/AIN5/VOUT1/SERCOM0.1_10") (pintype "bidirectional"))
      (node (ref "R1") (pin "1") (pinfunction "1_1") (pintype "passive"))
      (node (ref "R1") (pin "2") (pinfunction "1_2") (pintype "passive"))
      (node (ref "R10") (pin "8") (pinfunction "2_8") (pintype "passive"))
    )
    (net (code "4") (name "AGND") (class "Default")
      (node (ref "C16") (pin "2") (pinfunction "2_2") (pintype "passive"))
      (node (ref "C19") (pin "2") (pinfunction "2_2") (pintype "passive"))
      (node (ref "FB1") (pin "2") (pinfunction "P$2_2") (pintype "passive"))
      (node (ref "R1") (pin "6") (pinfunction "2_6") (pintype "passive"))
      (node (ref "R1") (pin "7") (pinfunction "2_7") (pintype "passive"))
      (node (ref "R10") (pin "6") (pinfunction "2_6") (pintype "passive"))
      (node (ref "R10") (pin "7") (pinfunction "2_7") (pintype "passive"))
      (node (ref "R6") (pin "1") (pinfunction "1_1") (pintype "passive"))
      (node (ref "U2") (pin "2") (pinfunction "GND_2") (pintype "bidirectional"))
      (node (ref "X4") (pin "4-INNER_SLEEVE") (pinfunction "RING1_4-INNER_SLEEVE") (pintype "passive"))
    )
    (net (code "5") (name "AVCC") (class "Default")
      (node (ref "FB2") (pin "1") (pinfunction "P$1_1") (pintype "passive"))
      (node (ref "R1") (pin "5") (pinfunction "2_5") (pintype "passive"))
      (node (ref "R1") (pin "8") (pinfunction "2_8") (pintype "passive"))
      (node (ref "R4") (pin "2") (pinfunction "2_2") (pintype "passive"))
      (node (ref "R7") (pin "2") (pinfunction "2_2") (pintype "passive"))
      (node (ref "U2") (pin "5") (pinfunction "VCC_5") (pintype "bidirectional"))
    )
    (net (code "6") (name "AVDD") (class "Default")
      (node (ref "C20") (pin "1") (pinfunction "1_1") (pintype "passive"))
      (node (ref "C21") (pin "1") (pinfunction "1_1") (pintype "passive"))
      (node (ref "C22") (pin "1") (pinfunction "1_1") (pintype "passive"))
      (node (ref "FB3") (pin "2") (pinfunction "P$2_2") (pintype "passive"))
      (node (ref "IC4") (pin "4") (pinfunction "PA03/I3/VREFA/AIN1_4") (pintype "bidirectional"))
      (node (ref "IC4") (pin "6") (pinfunction "VDDA_6") (pintype "power_in"))
    )
    (net (code "7") (name "COL0") (class "Default")
      (node (ref "IC4") (pin "23") (pinfunction "PA14/I14/SERCOM2+4.2_23") (pintype "bidirectional"))
      (node (ref "TP12") (pin "P$1") (pinfunction "P$1_P$1") (pintype "bidirectional"))
      (node (ref "U$12") (pin "P$1") (pinfunction "P$1_P$1") (pintype "bidirectional"))
      (node (ref "U$26") (pin "P$1") (pinfunction "P$1_P$1") (pintype "bidirectional"))
      (node (ref "U$4") (pin "P$1") (pinfunction "P$1_P$1") (pintype "bidirectional"))
      (node (ref "U$8") (pin "P$1") (pinfunction "P$1_P$1") (pintype "bidirectional"))
    )
    (net (code "8") (name "COL1") (class "Default")
      (node (ref "IC4") (pin "24") (pinfunction "PA15/I15/SERCOM2+4.3_24") (pintype "bidirectional"))
      (node (ref "TP13") (pin "P$1") (pinfunction "P$1_P$1") (pintype "bidirectional"))
      (node (ref "U$23") (pin "P$1") (pinfunction "P$1_P$1") (pintype "bidirectional"))
      (node (ref "U$27") (pin "P$1") (pinfunction "P$1_P$1") (pintype "bidirectional"))
      (node (ref "U$5") (pin "P$1") (pinfunction "P$1_P$1") (pintype "bidirectional"))
      (node (ref "U$9") (pin "P$1") (pinfunction "P$1_P$1") (pintype "bidirectional"))
    )
    (net (code "9") (name "COL2") (class "Default")
      (node (ref "IC4") (pin "25") (pinfunction "PA16/I2C/I0/SERCOM1.0+3.1_25") (pintype "bidirectional"))
      (node (ref "TP14") (pin "P$1") (pinfunction "P$1_P$1") (pintype "bidirectional"))
      (node (ref "U$10") (pin "P$1") (pinfunction "P$1_P$1") (pintype "bidirectional"))
      (node (ref "U$25") (pin "P$1") (pinfunction "P$1_P$1") (pintype "bidirectional"))
      (node (ref "U$28") (pin "P$1") (pinfunction "P$1_P$1") (pintype "bidirectional"))
      (node (ref "U$6") (pin "P$1") (pinfunction "P$1_P$1") (pintype "bidirectional"))
    )
    (net (code "10") (name "COL3") (class "Default")
      (node (ref "IC4") (pin "26") (pinfunction "PA17/I2C/I1/SERCOM1.1+3.0_26") (pintype "bidirectional"))
      (node (ref "TP15") (pin "P$1") (pinfunction "P$1_P$1") (pintype "bidirectional"))
      (node (ref "U$11") (pin "P$1") (pinfunction "P$1_P$1") (pintype "bidirectional"))
      (node (ref "U$24") (pin "P$1") (pinfunction "P$1_P$1") (pintype "bidirectional"))
      (node (ref "U$29") (pin "P$1") (pinfunction "P$1_P$1") (pintype "bidirectional"))
      (node (ref "U$7") (pin "P$1") (pinfunction "P$1_P$1") (pintype "bidirectional"))
    )
    (net (code "11") (name "COL4") (class "Default")
      (node (ref "IC4") (pin "29") (pinfunction "PA20/I4/SERCOM3+5.2/I2SFS0_29") (pintype "bidirectional"))
      (node (ref "TP16") (pin "P$1") (pinfunction "P$1_P$1") (pintype "bidirectional"))
      (node (ref "U$19") (pin "P$1") (pinfunction "P$1_P$1") (pintype "bidirectional"))
      (node (ref "U$36") (pin "P$1") (pinfunction "P$1_P$1") (pintype "bidirectional"))
      (node (ref "U$40") (pin "P$1") (pinfunction "P$1_P$1") (pintype "bidirectional"))
      (node (ref "U$44") (pin "P$1") (pinfunction "P$1_P$1") (pintype "bidirectional"))
    )
    (net (code "12") (name "COL5") (class "Default")
      (node (ref "IC4") (pin "30") (pinfunction "PA21/I5/SERCOM3+5.3/I2SDO_30") (pintype "bidirectional"))
      (node (ref "TP17") (pin "P$1") (pinfunction "P$1_P$1") (pintype "bidirectional"))
      (node (ref "U$33") (pin "P$1") (pinfunction "P$1_P$1") (pintype "bidirectional"))
      (node (ref "U$37") (pin "P$1") (pinfunction "P$1_P$1") (pintype "bidirectional"))
      (node (ref "U$41") (pin "P$1") (pinfunction "P$1_P$1") (pintype "bidirectional"))
      (node (ref "U$45") (pin "P$1") (pinfunction "P$1_P$1") (pintype "bidirectional"))
    )
    (net (code "13") (name "COL6") (class "Default")
      (node (ref "IC4") (pin "31") (pinfunction "PA22/I2C/I6/SERCOM3.0+5.1/I2SDI_31") (pintype "bidirectional"))
      (node (ref "TP18") (pin "P$1") (pinfunction "P$1_P$1") (pintype "bidirectional"))
      (node (ref "U$34") (pin "P$1") (pinfunction "P$1_P$1") (pintype "bidirectional"))
      (node (ref "U$38") (pin "P$1") (pinfunction "P$1_P$1") (pintype "bidirectional"))
      (node (ref "U$43") (pin "P$1") (pinfunction "P$1_P$1") (pintype "bidirectional"))
      (node (ref "U$46") (pin "P$1") (pinfunction "P$1_P$1") (pintype "bidirectional"))
    )
    (net (code "14") (name "COL7") (class "Default")
      (node (ref "IC4") (pin "32") (pinfunction "PA23/I2C/I7/SERCOM3.1+5.0/SOF/I2SFS1_32") (pintype "bidirectional"))
      (node (ref "TP19") (pin "P$1") (pinfunction "P$1_P$1") (pintype "bidirectional"))
      (node (ref "U$35") (pin "P$1") (pinfunction "P$1_P$1") (pintype "bidirectional"))
      (node (ref "U$39") (pin "P$1") (pinfunction "P$1_P$1") (pintype "bidirectional"))
      (node (ref "U$42") (pin "P$1") (pinfunction "P$1_P$1") (pintype "bidirectional"))
      (node (ref "U$47") (pin "P$1") (pinfunction "P$1_P$1") (pintype "bidirectional"))
    )
    (net (code "15") (name "D+") (class "Default")
      (node (ref "IC4") (pin "34") (pinfunction "PA25/I9/SERCOM3+5.3/D+_34") (pintype "bidirectional"))
      (node (ref "X3") (pin "D+") (pinfunction "D+_D+") (pintype "bidirectional"))
    )
    (net (code "16") (name "D-") (class "Default")
      (node (ref "IC4") (pin "33") (pinfunction "PA24/I8/SERCOM3+5.2/D-_33") (pintype "bidirectional"))
      (node (ref "X3") (pin "D-") (pinfunction "D-_D-") (pintype "bidirectional"))
    )
    (net (code "17") (name "DOTSTAR_CLK") (class "Default")
      (node (ref "IC4") (pin "47") (pinfunction "PB02/I2/AIN14/SERCOM5.0_47") (pintype "bidirectional"))
      (node (ref "L2") (pin "5") (pinfunction "CKI_5") (pintype "input"))
    )
    (net (code "18") (name "DOTSTAR_DATA") (class "Default")
      (node (ref "IC4") (pin "48") (pinfunction "PB03/I3/AIN15/SERCOM5.1_48") (pintype "bidirectional"))
      (node (ref "L2") (pin "6") (pinfunction "DI_6") (pintype "input"))
    )
    (net (code "19") (name "GND") (class "Default")
      (node (ref "C1") (pin "1") (pinfunction "1_1") (pintype "passive"))
      (node (ref "C10") (pin "2") (pinfunction "2_2") (pintype "passive"))
      (node (ref "C11") (pin "2") (pinfunction "2_2") (pintype "passive"))
      (node (ref "C12") (pin "2") (pinfunction "2_2") (pintype "passive"))
      (node (ref "C13") (pin "2") (pinfunction "2_2") (pintype "passive"))
      (node (ref "C14") (pin "2") (pinfunction "2_2") (pintype "passive"))
      (node (ref "C15") (pin "1") (pinfunction "1_1") (pintype "passive"))
      (node (ref "C2") (pin "1") (pinfunction "1_1") (pintype "passive"))
      (node (ref "C23") (pin "2") (pinfunction "2_2") (pintype "passive"))
      (node (ref "C3") (pin "1") (pinfunction "1_1") (pintype "passive"))
      (node (ref "C4") (pin "1") (pinfunction "1_1") (pintype "passive"))
      (node (ref "C5") (pin "1") (pinfunction "1_1") (pintype "passive"))
      (node (ref "C6") (pin "1") (pinfunction "1_1") (pintype "passive"))
      (node (ref "C9") (pin "2") (pinfunction "2_2") (pintype "passive"))
      (node (ref "CONN1") (pin "1") (pinfunction "GND_1") (pintype "passive"))
      (node (ref "FB1") (pin "1") (pinfunction "P$1_1") (pintype "passive"))
      (node (ref "FB4") (pin "1") (pinfunction "P$1_1") (pintype "passive"))
      (node (ref "IC1") (pin "1") (pinfunction "OE_1") (pintype "input"))
      (node (ref "IC1") (pin "3") (pinfunction "GND_3") (pintype "power_in"))
      (node (ref "IC4") (pin "18") (pinfunction "GND_18") (pintype "power_in"))
      (node (ref "IC4") (pin "35") (pinfunction "GND_35") (pintype "power_in"))
      (node (ref "IC4") (pin "42") (pinfunction "GND_42") (pintype "power_in"))
      (node (ref "IC4") (pin "THERMAL") (pinfunction "TP_THERMAL") (pintype "power_in"))
      (node (ref "JP1") (pin "3") (pinfunction "3_3") (pintype "passive"))
      (node (ref "JP2") (pin "3") (pinfunction "3_3") (pintype "passive"))
      (node (ref "JP3") (pin "3") (pinfunction "3_3") (pintype "passive"))
      (node (ref "JP4") (pin "3") (pinfunction "3_3") (pintype "passive"))
      (node (ref "L2") (pin "4") (pinfunction "GND_4") (pintype "power_in"))
      (node (ref "LED1") (pin "4") (pinfunction "GND_4") (pintype "power_in"))
      (node (ref "LED10") (pin "4") (pinfunction "GND_4") (pintype "power_in"))
      (node (ref "LED11") (pin "4") (pinfunction "GND_4") (pintype "power_in"))
      (node (ref "LED12") (pin "4") (pinfunction "GND_4") (pintype "power_in"))
      (node (ref "LED13") (pin "4") (pinfunction "GND_4") (pintype "power_in"))
      (node (ref "LED14") (pin "4") (pinfunction "GND_4") (pintype "power_in"))
      (node (ref "LED15") (pin "4") (pinfunction "GND_4") (pintype "power_in"))
      (node (ref "LED16") (pin "4") (pinfunction "GND_4") (pintype "power_in"))
      (node (ref "LED17") (pin "4") (pinfunction "GND_4") (pintype "power_in"))
      (node (ref "LED18") (pin "4") (pinfunction "GND_4") (pintype "power_in"))
      (node (ref "LED19") (pin "4") (pinfunction "GND_4") (pintype "power_in"))
      (node (ref "LED2") (pin "4") (pinfunction "GND_4") (pintype "power_in"))
      (node (ref "LED20") (pin "4") (pinfunction "GND_4") (pintype "power_in"))
      (node (ref "LED21") (pin "4") (pinfunction "GND_4") (pintype "power_in"))
      (node (ref "LED22") (pin "4") (pinfunction "GND_4") (pintype "power_in"))
      (node (ref "LED23") (pin "4") (pinfunction "GND_4") (pintype "power_in"))
      (node (ref "LED24") (pin "4") (pinfunction "GND_4") (pintype "power_in"))
      (node (ref "LED25") (pin "4") (pinfunction "GND_4") (pintype "power_in"))
      (node (ref "LED26") (pin "4") (pinfunction "GND_4") (pintype "power_in"))
      (node (ref "LED27") (pin "4") (pinfunction "GND_4") (pintype "power_in"))
      (node (ref "LED28") (pin "4") (pinfunction "GND_4") (pintype "power_in"))
      (node (ref "LED29") (pin "4") (pinfunction "GND_4") (pintype "power_in"))
      (node (ref "LED3") (pin "4") (pinfunction "GND_4") (pintype "power_in"))
      (node (ref "LED30") (pin "4") (pinfunction "GND_4") (pintype "power_in"))
      (node (ref "LED31") (pin "4") (pinfunction "GND_4") (pintype "power_in"))
      (node (ref "LED32") (pin "4") (pinfunction "GND_4") (pintype "power_in"))
      (node (ref "LED4") (pin "4") (pinfunction "GND_4") (pintype "power_in"))
      (node (ref "LED5") (pin "4") (pinfunction "GND_4") (pintype "power_in"))
      (node (ref "LED6") (pin "4") (pinfunction "GND_4") (pintype "power_in"))
      (node (ref "LED7") (pin "4") (pinfunction "GND_4") (pintype "power_in"))
      (node (ref "LED8") (pin "4") (pinfunction "GND_4") (pintype "power_in"))
      (node (ref "LED9") (pin "4") (pinfunction "GND_4") (pintype "power_in"))
      (node (ref "SW1") (pin "2") (pinfunction "S_2") (pintype "passive"))
      (node (ref "SW1") (pin "4") (pinfunction "S1_4") (pintype "passive"))
      (node (ref "TP1") (pin "P$1") (pinfunction "P$1_P$1") (pintype "bidirectional"))
      (node (ref "TP2") (pin "P$1") (pinfunction "P$1_P$1") (pintype "bidirectional"))
      (node (ref "TP3") (pin "P$1") (pinfunction "P$1_P$1") (pintype "bidirectional"))
      (node (ref "TP4") (pin "P$1") (pinfunction "P$1_P$1") (pintype "bidirectional"))
      (node (ref "U1") (pin "2") (pinfunction "GND_2") (pintype "power_in"))
      (node (ref "U3") (pin "4") (pinfunction "VSS_4") (pintype "bidirectional"))
      (node (ref "U4") (pin "12") (pinfunction "ADDR/SDO_12") (pintype "bidirectional"))
      (node (ref "U4") (pin "2") (pinfunction "GND_2") (pintype "bidirectional"))
      (node (ref "U4") (pin "4") (pinfunction "GND_4") (pintype "bidirectional"))
      (node (ref "U4") (pin "5") (pinfunction "GND_5") (pintype "bidirectional"))
      (node (ref "X2") (pin "3") (pinfunction "GND_3") (pintype "power_in"))
      (node (ref "X2") (pin "5") (pinfunction "GND_5") (pintype "power_in"))
      (node (ref "X3") (pin "BASE@1") (pinfunction "GND_BASE@1") (pintype "power_in"))
      (node (ref "X3") (pin "BASE@2") (pinfunction "GND_BASE@2") (pintype "power_in"))
      (node (ref "X3") (pin "GND") (pinfunction "GND_GND") (pintype "power_in"))
      (node (ref "X3") (pin "SPRT@1") (pinfunction "GND_SPRT@1") (pintype "power_in"))
      (node (ref "X3") (pin "SPRT@2") (pinfunction "GND_SPRT@2") (pintype "power_in"))
      (node (ref "X3") (pin "SPRT@3") (pinfunction "GND_SPRT@3") (pintype "power_in"))
      (node (ref "X3") (pin "SPRT@4") (pinfunction "GND_SPRT@4") (pintype "power_in"))
    )
    (net (code "20") (name "INT") (class "Default")
      (node (ref "IC4") (pin "9") (pinfunction "PA04/I4/VREFB/AIN4/SERCOM0.0_9") (pintype "bidirectional"))
      (node (ref "JP1") (pin "1") (pinfunction "1_1") (pintype "passive"))
      (node (ref "JP2") (pin "1") (pinfunction "1_1") (pintype "passive"))
      (node (ref "JP3") (pin "1") (pinfunction "1_1") (pintype "passive"))
      (node (ref "JP4") (pin "1") (pinfunction "1_1") (pintype "passive"))
      (node (ref "R2") (pin "2") (pinfunction "1_2") (pintype "passive"))
    )
    (net (code "21") (name "LEFT") (class "Default")
      (node (ref "C7") (pin "2") (pinfunction "2_2") (pintype "passive"))
      (node (ref "X4") (pin "2-TIP") (pinfunction "RING3_2-TIP") (pintype "passive"))
    )
    (net (code "22") (name "MIC_IN") (class "Default")
      (node (ref "C17") (pin "1") (pinfunction "1_1") (pintype "passive"))
      (node (ref "IC4") (pin "12") (pinfunction "PA07/I7/AIN7/SERCOM0.3_12") (pintype "bidirectional"))
      (node (ref "R3") (pin "1") (pinfunction "1_1") (pintype "passive"))
      (node (ref "X4") (pin "1-GND") (pinfunction "TIP_1-GND") (pintype "passive"))
    )
    (net (code "23") (name "MIC_OUT") (class "Default")
      (node (ref "C18") (pin "1") (pinfunction "1_1") (pintype "passive"))
      (node (ref "IC4") (pin "11") (pinfunction "PA06/I6/VREFC/AIN6/SERCOM0.2_11") (pintype "bidirectional"))
      (node (ref "R8") (pin "2") (pinfunction "2_2") (pintype "passive"))
      (node (ref "U2") (pin "4") (pinfunction "OUT_4") (pintype "bidirectional"))
    )
    (net (code "24") (name "NEOPIXEL_3V") (class "Default")
      (node (ref "IC1") (pin "2") (pinfunction "I_2") (pintype "input"))
      (node (ref "IC4") (pin "39") (pinfunction "PA27/I11_39") (pintype "bidirectional"))
    )
    (net (code "25") (name "NEOPIXEL_5V") (class "Default")
      (node (ref "IC1") (pin "4") (pinfunction "O_4") (pintype "tri_state"))
      (node (ref "LED1") (pin "1") (pinfunction "DI_1") (pintype "input"))
    )
    (net (code "26") (name "Net-(C16-Pad1)") (class "Default")
      (node (ref "C16") (pin "1") (pinfunction "1_1") (pintype "passive"))
      (node (ref "R3") (pin "2") (pinfunction "2_2") (pintype "passive"))
      (node (ref "R4") (pin "1") (pinfunction "1_1") (pintype "passive"))
    )
    (net (code "27") (name "Net-(C19-Pad1)") (class "Default")
      (node (ref "C19") (pin "1") (pinfunction "1_1") (pintype "passive"))
      (node (ref "R5") (pin "2") (pinfunction "2_2") (pintype "passive"))
    )
    (net (code "28") (name "Net-(D1-PadC)") (class "Default")
      (node (ref "D1") (pin "C") (pinfunction "C_C") (pintype "passive"))
      (node (ref "TP21") (pin "P$1") (pinfunction "P$1_P$1") (pintype "bidirectional"))
      (node (ref "U$5") (pin "P$2") (pinfunction "P$2_P$2") (pintype "bidirectional"))
    )
    (net (code "29") (name "Net-(D2-PadC)") (class "Default")
      (node (ref "D2") (pin "C") (pinfunction "C_C") (pintype "passive"))
      (node (ref "TP22") (pin "P$1") (pinfunction "P$1_P$1") (pintype "bidirectional"))
      (node (ref "U$6") (pin "P$2") (pinfunction "P$2_P$2") (pintype "bidirectional"))
    )
    (net (code "30") (name "Net-(D3-PadC)") (class "Default")
      (node (ref "D3") (pin "C") (pinfunction "C_C") (pintype "passive"))
      (node (ref "TP23") (pin "P$1") (pinfunction "P$1_P$1") (pintype "bidirectional"))
      (node (ref "U$7") (pin "P$2") (pinfunction "P$2_P$2") (pintype "bidirectional"))
    )
    (net (code "31") (name "Net-(D4-PadC)") (class "Default")
      (node (ref "D4") (pin "C") (pinfunction "C_C") (pintype "passive"))
      (node (ref "TP8") (pin "P$1") (pinfunction "P$1_P$1") (pintype "bidirectional"))
      (node (ref "U$8") (pin "P$2") (pinfunction "P$2_P$2") (pintype "bidirectional"))
    )
    (net (code "32") (name "Net-(D5-PadC)") (class "Default")
      (node (ref "D5") (pin "C") (pinfunction "C_C") (pintype "passive"))
      (node (ref "TP24") (pin "P$1") (pinfunction "P$1_P$1") (pintype "bidirectional"))
      (node (ref "U$9") (pin "P$2") (pinfunction "P$2_P$2") (pintype "bidirectional"))
    )
    (net (code "33") (name "Net-(D6-PadC)") (class "Default")
      (node (ref "D6") (pin "C") (pinfunction "C_C") (pintype "passive"))
      (node (ref "TP34") (pin "P$1") (pinfunction "P$1_P$1") (pintype "bidirectional"))
      (node (ref "U$10") (pin "P$2") (pinfunction "P$2_P$2") (pintype "bidirectional"))
    )
    (net (code "34") (name "Net-(D7-PadC)") (class "Default")
      (node (ref "D7") (pin "C") (pinfunction "C_C") (pintype "passive"))
      (node (ref "TP25") (pin "P$1") (pinfunction "P$1_P$1") (pintype "bidirectional"))
      (node (ref "U$11") (pin "P$2") (pinfunction "P$2_P$2") (pintype "bidirectional"))
    )
    (net (code "35") (name "Net-(D8-PadC)") (class "Default")
      (node (ref "D8") (pin "C") (pinfunction "C_C") (pintype "passive"))
      (node (ref "TP33") (pin "P$1") (pinfunction "P$1_P$1") (pintype "bidirectional"))
      (node (ref "U$12") (pin "P$2") (pinfunction "P$2_P$2") (pintype "bidirectional"))
    )
    (net (code "36") (name "Net-(D9-PadC)") (class "Default")
      (node (ref "D9") (pin "C") (pinfunction "C_C") (pintype "passive"))
      (node (ref "TP20") (pin "P$1") (pinfunction "P$1_P$1") (pintype "bidirectional"))
      (node (ref "U$4") (pin "P$2") (pinfunction "P$2_P$2") (pintype "bidirectional"))
    )
    (net (code "37") (name "Net-(D10-PadC)") (class "Default")
      (node (ref "D10") (pin "C") (pinfunction "C_C") (pintype "passive"))
      (node (ref "TP26") (pin "P$1") (pinfunction "P$1_P$1") (pintype "bidirectional"))
      (node (ref "U$23") (pin "P$2") (pinfunction "P$2_P$2") (pintype "bidirectional"))
    )
    (net (code "38") (name "Net-(D11-PadC)") (class "Default")
      (node (ref "D11") (pin "C") (pinfunction "C_C") (pintype "passive"))
      (node (ref "TP32") (pin "P$1") (pinfunction "P$1_P$1") (pintype "bidirectional"))
      (node (ref "U$25") (pin "P$2") (pinfunction "P$2_P$2") (pintype "bidirectional"))
    )
    (net (code "39") (name "Net-(D12-PadC)") (class "Default")
      (node (ref "D12") (pin "C") (pinfunction "C_C") (pintype "passive"))
      (node (ref "TP27") (pin "P$1") (pinfunction "P$1_P$1") (pintype "bidirectional"))
      (node (ref "U$24") (pin "P$2") (pinfunction "P$2_P$2") (pintype "bidirectional"))
    )
    (net (code "40") (name "Net-(D13-PadC)") (class "Default")
      (node (ref "D13") (pin "C") (pinfunction "C_C") (pintype "passive"))
      (node (ref "TP31") (pin "P$1") (pinfunction "P$1_P$1") (pintype "bidirectional"))
      (node (ref "U$26") (pin "P$2") (pinfunction "P$2_P$2") (pintype "bidirectional"))
    )
    (net (code "41") (name "Net-(D14-PadC)") (class "Default")
      (node (ref "D14") (pin "C") (pinfunction "C_C") (pintype "passive"))
      (node (ref "TP28") (pin "P$1") (pinfunction "P$1_P$1") (pintype "bidirectional"))
      (node (ref "U$27") (pin "P$2") (pinfunction "P$2_P$2") (pintype "bidirectional"))
    )
    (net (code "42") (name "Net-(D15-PadC)") (class "Default")
      (node (ref "D15") (pin "C") (pinfunction "C_C") (pintype "passive"))
      (node (ref "TP30") (pin "P$1") (pinfunction "P$1_P$1") (pintype "bidirectional"))
      (node (ref "U$28") (pin "P$2") (pinfunction "P$2_P$2") (pintype "bidirectional"))
    )
    (net (code "43") (name "Net-(D16-PadC)") (class "Default")
      (node (ref "D16") (pin "C") (pinfunction "C_C") (pintype "passive"))
      (node (ref "TP29") (pin "P$1") (pinfunction "P$1_P$1") (pintype "bidirectional"))
      (node (ref "U$29") (pin "P$2") (pinfunction "P$2_P$2") (pintype "bidirectional"))
    )
    (net (code "44") (name "Net-(D17-PadC)") (class "Default")
      (node (ref "D17") (pin "C") (pinfunction "C_C") (pintype "passive"))
      (node (ref "TP35") (pin "P$1") (pinfunction "P$1_P$1") (pintype "bidirectional"))
      (node (ref "U$19") (pin "P$2") (pinfunction "P$2_P$2") (pintype "bidirectional"))
    )
    (net (code "45") (name "Net-(D18-PadC)") (class "Default")
      (node (ref "D18") (pin "C") (pinfunction "C_C") (pintype "passive"))
      (node (ref "TP36") (pin "P$1") (pinfunction "P$1_P$1") (pintype "bidirectional"))
      (node (ref "U$33") (pin "P$2") (pinfunction "P$2_P$2") (pintype "bidirectional"))
    )
    (net (code "46") (name "Net-(D19-PadC)") (class "Default")
      (node (ref "D19") (pin "C") (pinfunction "C_C") (pintype "passive"))
      (node (ref "TP38") (pin "P$1") (pinfunction "P$1_P$1") (pintype "bidirectional"))
      (node (ref "U$34") (pin "P$2") (pinfunction "P$2_P$2") (pintype "bidirectional"))
    )
    (net (code "47") (name "Net-(D20-PadC)") (class "Default")
      (node (ref "D20") (pin "C") (pinfunction "C_C") (pintype "passive"))
      (node (ref "TP37") (pin "P$1") (pinfunction "P$1_P$1") (pintype "bidirectional"))
      (node (ref "U$35") (pin "P$2") (pinfunction "P$2_P$2") (pintype "bidirectional"))
    )
    (net (code "48") (name "Net-(D21-PadC)") (class "Default")
      (node (ref "D21") (pin "C") (pinfunction "C_C") (pintype "passive"))
      (node (ref "TP39") (pin "P$1") (pinfunction "P$1_P$1") (pintype "bidirectional"))
      (node (ref "U$36") (pin "P$2") (pinfunction "P$2_P$2") (pintype "bidirectional"))
    )
    (net (code "49") (name "Net-(D22-PadC)") (class "Default")
      (node (ref "D22") (pin "C") (pinfunction "C_C") (pintype "passive"))
      (node (ref "TP40") (pin "P$1") (pinfunction "P$1_P$1") (pintype "bidirectional"))
      (node (ref "U$37") (pin "P$2") (pinfunction "P$2_P$2") (pintype "bidirectional"))
    )
    (net (code "50") (name "Net-(D23-PadC)") (class "Default")
      (node (ref "D23") (pin "C") (pinfunction "C_C") (pintype "passive"))
      (node (ref "TP42") (pin "P$1") (pinfunction "P$1_P$1") (pintype "bidirectional"))
      (node (ref "U$38") (pin "P$2") (pinfunction "P$2_P$2") (pintype "bidirectional"))
    )
    (net (code "51") (name "Net-(D24-PadC)") (class "Default")
      (node (ref "D24") (pin "C") (pinfunction "C_C") (pintype "passive"))
      (node (ref "TP41") (pin "P$1") (pinfunction "P$1_P$1") (pintype "bidirectional"))
      (node (ref "U$39") (pin "P$2") (pinfunction "P$2_P$2") (pintype "bidirectional"))
    )
    (net (code "52") (name "Net-(D25-PadC)") (class "Default")
      (node (ref "D25") (pin "C") (pinfunction "C_C") (pintype "passive"))
      (node (ref "TP43") (pin "P$1") (pinfunction "P$1_P$1") (pintype "bidirectional"))
      (node (ref "U$40") (pin "P$2") (pinfunction "P$2_P$2") (pintype "bidirectional"))
    )
    (net (code "53") (name "Net-(D26-PadC)") (class "Default")
      (node (ref "D26") (pin "C") (pinfunction "C_C") (pintype "passive"))
      (node (ref "TP44") (pin "P$1") (pinfunction "P$1_P$1") (pintype "bidirectional"))
      (node (ref "U$41") (pin "P$2") (pinfunction "P$2_P$2") (pintype "bidirectional"))
    )
    (net (code "54") (name "Net-(D27-PadC)") (class "Default")
      (node (ref "D27") (pin "C") (pinfunction "C_C") (pintype "passive"))
      (node (ref "TP46") (pin "P$1") (pinfunction "P$1_P$1") (pintype "bidirectional"))
      (node (ref "U$43") (pin "P$2") (pinfunction "P$2_P$2") (pintype "bidirectional"))
    )
    (net (code "55") (name "Net-(D28-PadC)") (class "Default")
      (node (ref "D28") (pin "C") (pinfunction "C_C") (pintype "passive"))
      (node (ref "TP45") (pin "P$1") (pinfunction "P$1_P$1") (pintype "bidirectional"))
      (node (ref "U$42") (pin "P$2") (pinfunction "P$2_P$2") (pintype "bidirectional"))
    )
    (net (code "56") (name "Net-(D29-PadC)") (class "Default")
      (node (ref "D29") (pin "C") (pinfunction "C_C") (pintype "passive"))
      (node (ref "TP47") (pin "P$1") (pinfunction "P$1_P$1") (pintype "bidirectional"))
      (node (ref "U$44") (pin "P$2") (pinfunction "P$2_P$2") (pintype "bidirectional"))
    )
    (net (code "57") (name "Net-(D30-PadC)") (class "Default")
      (node (ref "D30") (pin "C") (pinfunction "C_C") (pintype "passive"))
      (node (ref "TP49") (pin "P$1") (pinfunction "P$1_P$1") (pintype "bidirectional"))
      (node (ref "U$45") (pin "P$2") (pinfunction "P$2_P$2") (pintype "bidirectional"))
    )
    (net (code "58") (name "Net-(D31-PadC)") (class "Default")
      (node (ref "D31") (pin "C") (pinfunction "C_C") (pintype "passive"))
      (node (ref "TP48") (pin "P$1") (pinfunction "P$1_P$1") (pintype "bidirectional"))
      (node (ref "U$46") (pin "P$2") (pinfunction "P$2_P$2") (pintype "bidirectional"))
    )
    (net (code "59") (name "Net-(D32-PadC)") (class "Default")
      (node (ref "D32") (pin "C") (pinfunction "C_C") (pintype "passive"))
      (node (ref "TP50") (pin "P$1") (pinfunction "P$1_P$1") (pintype "bidirectional"))
      (node (ref "U$47") (pin "P$2") (pinfunction "P$2_P$2") (pintype "bidirectional"))
    )
    (net (code "60") (name "Net-(IC4A-VDDCORE)") (class "Default")
      (node (ref "C13") (pin "1") (pinfunction "1_1") (pintype "passive"))
      (node (ref "IC4") (pin "41") (pinfunction "VDDCORE_41") (pintype "power_in"))
    )
    (net (code "61") (name "Net-(LED1-DO)") (class "Default")
      (node (ref "LED1") (pin "3") (pinfunction "DO_3") (pintype "output"))
      (node (ref "LED2") (pin "1") (pinfunction "DI_1") (pintype "input"))
    )
    (net (code "62") (name "Net-(LED2-DO)") (class "Default")
      (node (ref "LED2") (pin "3") (pinfunction "DO_3") (pintype "output"))
      (node (ref "LED3") (pin "1") (pinfunction "DI_1") (pintype "input"))
    )
    (net (code "63") (name "Net-(LED3-DO)") (class "Default")
      (node (ref "LED3") (pin "3") (pinfunction "DO_3") (pintype "output"))
      (node (ref "LED4") (pin "1") (pinfunction "DI_1") (pintype "input"))
    )
    (net (code "64") (name "Net-(LED4-DO)") (class "Default")
      (node (ref "LED4") (pin "3") (pinfunction "DO_3") (pintype "output"))
      (node (ref "LED5") (pin "1") (pinfunction "DI_1") (pintype "input"))
    )
    (net (code "65") (name "Net-(LED5-DO)") (class "Default")
      (node (ref "LED5") (pin "3") (pinfunction "DO_3") (pintype "output"))
      (node (ref "LED6") (pin "1") (pinfunction "DI_1") (pintype "input"))
    )
    (net (code "66") (name "Net-(LED6-DO)") (class "Default")
      (node (ref "LED6") (pin "3") (pinfunction "DO_3") (pintype "output"))
      (node (ref "LED7") (pin "1") (pinfunction "DI_1") (pintype "input"))
    )
    (net (code "67") (name "Net-(LED7-DO)") (class "Default")
      (node (ref "LED7") (pin "3") (pinfunction "DO_3") (pintype "output"))
      (node (ref "LED8") (pin "1") (pinfunction "DI_1") (pintype "input"))
    )
    (net (code "68") (name "Net-(LED8-DO)") (class "Default")
      (node (ref "LED8") (pin "3") (pinfunction "DO_3") (pintype "output"))
      (node (ref "LED9") (pin "1") (pinfunction "DI_1") (pintype "input"))
    )
    (net (code "69") (name "Net-(LED10-DI)") (class "Default")
      (node (ref "LED10") (pin "1") (pinfunction "DI_1") (pintype "input"))
      (node (ref "LED9") (pin "3") (pinfunction "DO_3") (pintype "output"))
    )
    (net (code "70") (name "Net-(LED10-DO)") (class "Default")
      (node (ref "LED10") (pin "3") (pinfunction "DO_3") (pintype "output"))
      (node (ref "LED12") (pin "1") (pinfunction "DI_1") (pintype "input"))
    )
    (net (code "71") (name "Net-(LED11-DI)") (class "Default")
      (node (ref "LED11") (pin "1") (pinfunction "DI_1") (pintype "input"))
      (node (ref "LED12") (pin "3") (pinfunction "DO_3") (pintype "output"))
    )
    (net (code "72") (name "Net-(LED11-DO)") (class "Default")
      (node (ref "LED11") (pin "3") (pinfunction "DO_3") (pintype "output"))
      (node (ref "LED13") (pin "1") (pinfunction "DI_1") (pintype "input"))
    )
    (net (code "73") (name "Net-(LED13-DO)") (class "Default")
      (node (ref "LED13") (pin "3") (pinfunction "DO_3") (pintype "output"))
      (node (ref "LED14") (pin "1") (pinfunction "DI_1") (pintype "input"))
    )
    (net (code "74") (name "Net-(LED14-DO)") (class "Default")
      (node (ref "LED14") (pin "3") (pinfunction "DO_3") (pintype "output"))
      (node (ref "LED15") (pin "1") (pinfunction "DI_1") (pintype "input"))
    )
    (net (code "75") (name "Net-(LED15-DO)") (class "Default")
      (node (ref "LED15") (pin "3") (pinfunction "DO_3") (pintype "output"))
      (node (ref "LED16") (pin "1") (pinfunction "DI_1") (pintype "input"))
    )
    (net (code "76") (name "Net-(LED16-DO)") (class "Default")
      (node (ref "LED16") (pin "3") (pinfunction "DO_3") (pintype "output"))
      (node (ref "LED17") (pin "1") (pinfunction "DI_1") (pintype "input"))
    )
    (net (code "77") (name "Net-(LED17-DO)") (class "Default")
      (node (ref "LED17") (pin "3") (pinfunction "DO_3") (pintype "output"))
      (node (ref "LED18") (pin "1") (pinfunction "DI_1") (pintype "input"))
    )
    (net (code "78") (name "Net-(LED18-DO)") (class "Default")
      (node (ref "LED18") (pin "3") (pinfunction "DO_3") (pintype "output"))
      (node (ref "LED19") (pin "1") (pinfunction "DI_1") (pintype "input"))
    )
    (net (code "79") (name "Net-(LED19-DO)") (class "Default")
      (node (ref "LED19") (pin "3") (pinfunction "DO_3") (pintype "output"))
      (node (ref "LED20") (pin "1") (pinfunction "DI_1") (pintype "input"))
    )
    (net (code "80") (name "Net-(LED20-DO)") (class "Default")
      (node (ref "LED20") (pin "3") (pinfunction "DO_3") (pintype "output"))
      (node (ref "LED21") (pin "1") (pinfunction "DI_1") (pintype "input"))
    )
    (net (code "81") (name "Net-(LED21-DO)") (class "Default")
      (node (ref "LED21") (pin "3") (pinfunction "DO_3") (pintype "output"))
      (node (ref "LED22") (pin "1") (pinfunction "DI_1") (pintype "input"))
    )
    (net (code "82") (name "Net-(LED22-DO)") (class "Default")
      (node (ref "LED22") (pin "3") (pinfunction "DO_3") (pintype "output"))
      (node (ref "LED23") (pin "1") (pinfunction "DI_1") (pintype "input"))
    )
    (net (code "83") (name "Net-(LED23-DO)") (class "Default")
      (node (ref "LED23") (pin "3") (pinfunction "DO_3") (pintype "output"))
      (node (ref "LED24") (pin "1") (pinfunction "DI_1") (pintype "input"))
    )
    (net (code "84") (name "Net-(LED24-DO)") (class "Default")
      (node (ref "LED24") (pin "3") (pinfunction "DO_3") (pintype "output"))
      (node (ref "LED25") (pin "1") (pinfunction "DI_1") (pintype "input"))
    )
    (net (code "85") (name "Net-(LED25-DO)") (class "Default")
      (node (ref "LED25") (pin "3") (pinfunction "DO_3") (pintype "output"))
      (node (ref "LED26") (pin "1") (pinfunction "DI_1") (pintype "input"))
    )
    (net (code "86") (name "Net-(LED26-DO)") (class "Default")
      (node (ref "LED26") (pin "3") (pinfunction "DO_3") (pintype "output"))
      (node (ref "LED28") (pin "1") (pinfunction "DI_1") (pintype "input"))
    )
    (net (code "87") (name "Net-(LED27-DI)") (class "Default")
      (node (ref "LED27") (pin "1") (pinfunction "DI_1") (pintype "input"))
      (node (ref "LED28") (pin "3") (pinfunction "DO_3") (pintype "output"))
    )
    (net (code "88") (name "Net-(LED27-DO)") (class "Default")
      (node (ref "LED27") (pin "3") (pinfunction "DO_3") (pintype "output"))
      (node (ref "LED29") (pin "1") (pinfunction "DI_1") (pintype "input"))
    )
    (net (code "89") (name "Net-(LED29-DO)") (class "Default")
      (node (ref "LED29") (pin "3") (pinfunction "DO_3") (pintype "output"))
      (node (ref "LED30") (pin "1") (pinfunction "DI_1") (pintype "input"))
    )
    (net (code "90") (name "Net-(LED30-DO)") (class "Default")
      (node (ref "LED30") (pin "3") (pinfunction "DO_3") (pintype "output"))
      (node (ref "LED31") (pin "1") (pinfunction "DI_1") (pintype "input"))
    )
    (net (code "91") (name "Net-(LED31-DO)") (class "Default")
      (node (ref "LED31") (pin "3") (pinfunction "DO_3") (pintype "output"))
      (node (ref "LED32") (pin "1") (pinfunction "DI_1") (pintype "input"))
    )
    (net (code "92") (name "Net-(PTC1-Pad2)") (class "Default")
      (node (ref "PTC1") (pin "2") (pinfunction "2_2") (pintype "passive"))
      (node (ref "X3") (pin "VBUS") (pinfunction "VBUS_VBUS") (pintype "power_in"))
    )
    (net (code "93") (name "Net-(R10B-1)") (class "Default")
      (node (ref "C7") (pin "1") (pinfunction "1_1") (pintype "passive"))
      (node (ref "R10") (pin "1") (pinfunction "1_1") (pintype "passive"))
      (node (ref "R10") (pin "2") (pinfunction "1_2") (pintype "passive"))
    )
    (net (code "94") (name "Net-(R10C-1)") (class "Default")
      (node (ref "C8") (pin "1") (pinfunction "1_1") (pintype "passive"))
      (node (ref "R10") (pin "3") (pinfunction "1_3") (pintype "passive"))
      (node (ref "R10") (pin "4") (pinfunction "1_4") (pintype "passive"))
    )
    (net (code "95") (name "Net-(U2-IN+)") (class "Default")
      (node (ref "C17") (pin "2") (pinfunction "2_2") (pintype "passive"))
      (node (ref "R6") (pin "2") (pinfunction "2_2") (pintype "passive"))
      (node (ref "R7") (pin "1") (pinfunction "1_1") (pintype "passive"))
      (node (ref "U2") (pin "1") (pinfunction "IN+_1") (pintype "bidirectional"))
    )
    (net (code "96") (name "Net-(U2-IN-)") (class "Default")
      (node (ref "C18") (pin "2") (pinfunction "2_2") (pintype "passive"))
      (node (ref "R5") (pin "1") (pinfunction "1_1") (pintype "passive"))
      (node (ref "R8") (pin "1") (pinfunction "1_1") (pintype "passive"))
      (node (ref "U2") (pin "3") (pinfunction "IN-_3") (pintype "bidirectional"))
    )
    (net (code "97") (name "QSPI_CS") (class "Default")
      (node (ref "IC4") (pin "20") (pinfunction "PB11/I11/SERCOM4.3/I2SFS1_20") (pintype "bidirectional"))
      (node (ref "R9") (pin "2") (pinfunction "2_2") (pintype "passive"))
      (node (ref "U3") (pin "1") (pinfunction "SSEL_1") (pintype "bidirectional"))
    )
    (net (code "98") (name "QSPI_DATA[0]") (class "Default")
      (node (ref "IC4") (pin "13") (pinfunction "PA08/I2C/AIN8/SERCOM0.0+2.1/I2SMCK_13") (pintype "bidirectional"))
      (node (ref "U3") (pin "5") (pinfunction "MOSI_5") (pintype "bidirectional"))
    )
    (net (code "99") (name "QSPI_DATA[1]") (class "Default")
      (node (ref "IC4") (pin "14") (pinfunction "PA09/I2C/I9/AIN9/SERCOM0.1+2.0/I2SFS0_14") (pintype "bidirectional"))
      (node (ref "U3") (pin "2") (pinfunction "MISO_2") (pintype "bidirectional"))
    )
    (net (code "100") (name "QSPI_DATA[2]") (class "Default")
      (node (ref "IC4") (pin "15") (pinfunction "PA10/I10/AIN10/SERCOM0+2.2/I2SCK_15") (pintype "bidirectional"))
      (node (ref "U3") (pin "3") (pinfunction "WP#/IO2_3") (pintype "bidirectional"))
    )
    (net (code "101") (name "QSPI_DATA[3]") (class "Default")
      (node (ref "IC4") (pin "16") (pinfunction "PA11/I11/AIN11/SERCOM0+2.3/I2SDO_16") (pintype "bidirectional"))
      (node (ref "U3") (pin "7") (pinfunction "HOLD#/IO3_7") (pintype "bidirectional"))
    )
    (net (code "102") (name "QSPI_SCK") (class "Default")
      (node (ref "IC4") (pin "19") (pinfunction "PB10/I10/SERCOM4.2/I2SDI_19") (pintype "bidirectional"))
      (node (ref "U3") (pin "6") (pinfunction "SCK_6") (pintype "bidirectional"))
    )
    (net (code "103") (name "RIGHT") (class "Default")
      (node (ref "C8") (pin "2") (pinfunction "2_2") (pintype "passive"))
      (node (ref "X4") (pin "3-OUTER_SLEEVE") (pinfunction "RING2_3-OUTER_SLEEVE") (pintype "passive"))
    )
    (net (code "104") (name "ROW0") (class "Default")
      (node (ref "D1") (pin "A") (pinfunction "A_A") (pintype "passive"))
      (node (ref "D17") (pin "A") (pinfunction "A_A") (pintype "passive"))
      (node (ref "D18") (pin "A") (pinfunction "A_A") (pintype "passive"))
      (node (ref "D19") (pin "A") (pinfunction "A_A") (pintype "passive"))
      (node (ref "D2") (pin "A") (pinfunction "A_A") (pintype "passive"))
      (node (ref "D20") (pin "A") (pinfunction "A_A") (pintype "passive"))
      (node (ref "D3") (pin "A") (pinfunction "A_A") (pintype "passive"))
      (node (ref "D9") (pin "A") (pinfunction "A_A") (pintype "passive"))
      (node (ref "IC4") (pin "27") (pinfunction "PA18/I2/SERCOM1+3.2_27") (pintype "bidirectional"))
    )
    (net (code "105") (name "ROW1") (class "Default")
      (node (ref "D21") (pin "A") (pinfunction "A_A") (pintype "passive"))
      (node (ref "D22") (pin "A") (pinfunction "A_A") (pintype "passive"))
      (node (ref "D23") (pin "A") (pinfunction "A_A") (pintype "passive"))
      (node (ref "D24") (pin "A") (pinfunction "A_A") (pintype "passive"))
      (node (ref "D4") (pin "A") (pinfunction "A_A") (pintype "passive"))
      (node (ref "D5") (pin "A") (pinfunction "A_A") (pintype "passive"))
      (node (ref "D6") (pin "A") (pinfunction "A_A") (pintype "passive"))
      (node (ref "D7") (pin "A") (pinfunction "A_A") (pintype "passive"))
      (node (ref "IC4") (pin "28") (pinfunction "PA19/I3/SERCOM1+3.3_28") (pintype "bidirectional"))
    )
    (net (code "106") (name "ROW2") (class "Default")
      (node (ref "D10") (pin "A") (pinfunction "A_A") (pintype "passive"))
      (node (ref "D11") (pin "A") (pinfunction "A_A") (pintype "passive"))
      (node (ref "D12") (pin "A") (pinfunction "A_A") (pintype "passive"))
      (node (ref "D25") (pin "A") (pinfunction "A_A") (pintype "passive"))
      (node (ref "D26") (pin "A") (pinfunction "A_A") (pintype "passive"))
      (node (ref "D27") (pin "A") (pinfunction "A_A") (pintype "passive"))
      (node (ref "D28") (pin "A") (pinfunction "A_A") (pintype "passive"))
      (node (ref "D8") (pin "A") (pinfunction "A_A") (pintype "passive"))
      (node (ref "IC4") (pin "37") (pinfunction "PB22/I6/SERCOM1+5.2_37") (pintype "bidirectional"))
    )
    (net (code "107") (name "ROW3") (class "Default")
      (node (ref "D13") (pin "A") (pinfunction "A_A") (pintype "passive"))
      (node (ref "D14") (pin "A") (pinfunction "A_A") (pintype "passive"))
      (node (ref "D15") (pin "A") (pinfunction "A_A") (pintype "passive"))
      (node (ref "D16") (pin "A") (pinfunction "A_A") (pintype "passive"))
      (node (ref "D29") (pin "A") (pinfunction "A_A") (pintype "passive"))
      (node (ref "D30") (pin "A") (pinfunction "A_A") (pintype "passive"))
      (node (ref "D31") (pin "A") (pinfunction "A_A") (pintype "passive"))
      (node (ref "D32") (pin "A") (pinfunction "A_A") (pintype "passive"))
      (node (ref "IC4") (pin "38") (pinfunction "PB23/I7/SERCOM1+5.3_38") (pintype "bidirectional"))
    )
    (net (code "108") (name "SCL") (class "Default")
      (node (ref "CONN1") (pin "4") (pinfunction "SCL_4") (pintype "passive"))
      (node (ref "IC4") (pin "8") (pinfunction "PB09/I9/AIN3/SERCOM4.1_8") (pintype "bidirectional"))
      (node (ref "JP1") (pin "4") (pinfunction "4_4") (pintype "passive"))
      (node (ref "JP2") (pin "4") (pinfunction "4_4") (pintype "passive"))
      (node (ref "JP3") (pin "4") (pinfunction "4_4") (pintype "passive"))
      (node (ref "JP4") (pin "4") (pinfunction "4_4") (pintype "passive"))
      (node (ref "R2") (pin "4") (pinfunction "1_4") (pintype "passive"))
    )
    (net (code "109") (name "SCL1") (class "Default")
      (node (ref "IC4") (pin "22") (pinfunction "PA13/I13/I2C/SERCOM2.1+4.0_22") (pintype "bidirectional"))
      (node (ref "R13") (pin "2") (pinfunction "2_2") (pintype "passive"))
      (node (ref "U4") (pin "14") (pinfunction "SCL_14") (pintype "bidirectional"))
    )
    (net (code "110") (name "SDA") (class "Default")
      (node (ref "CONN1") (pin "3") (pinfunction "SDA_3") (pintype "passive"))
      (node (ref "IC4") (pin "7") (pinfunction "PB08/I8/AIN2/SERCOM4.0_7") (pintype "bidirectional"))
      (node (ref "JP1") (pin "5") (pinfunction "5_5") (pintype "passive"))
      (node (ref "JP2") (pin "5") (pinfunction "5_5") (pintype "passive"))
      (node (ref "JP3") (pin "5") (pinfunction "5_5") (pintype "passive"))
      (node (ref "JP4") (pin "5") (pinfunction "5_5") (pintype "passive"))
      (node (ref "R2") (pin "3") (pinfunction "1_3") (pintype "passive"))
    )
    (net (code "111") (name "SDA1") (class "Default")
      (node (ref "IC4") (pin "21") (pinfunction "PA12/I12/I2C/SERCOM2.0+4.1_21") (pintype "bidirectional"))
      (node (ref "R12") (pin "2") (pinfunction "2_2") (pintype "passive"))
      (node (ref "U4") (pin "13") (pinfunction "SDA_13") (pintype "bidirectional"))
    )
    (net (code "112") (name "SWCLK") (class "Default")
      (node (ref "IC4") (pin "45") (pinfunction "PA30/I14/SECOM1.2/SWCLK_45") (pintype "bidirectional"))
      (node (ref "R11") (pin "1") (pinfunction "1_1") (pintype "passive"))
      (node (ref "TP5") (pin "P$1") (pinfunction "P$1_P$1") (pintype "bidirectional"))
      (node (ref "X2") (pin "4") (pinfunction "SWDCLK_4") (pintype "bidirectional"))
    )
    (net (code "113") (name "SWDIO") (class "Default")
      (node (ref "IC4") (pin "46") (pinfunction "PA31/I15/SECOM1.3/SWDIO_46") (pintype "bidirectional"))
      (node (ref "TP6") (pin "P$1") (pinfunction "P$1_P$1") (pintype "bidirectional"))
      (node (ref "X2") (pin "2") (pinfunction "SWDIO_2") (pintype "bidirectional"))
    )
    (net (code "114") (name "VBUS") (class "Default")
      (node (ref "D34") (pin "A") (pinfunction "A_A") (pintype "passive"))
      (node (ref "PTC1") (pin "1") (pinfunction "1_1") (pintype "passive"))
    )
    (net (code "115") (name "VDD") (class "Default")
      (node (ref "C1") (pin "2") (pinfunction "2_2") (pintype "passive"))
      (node (ref "C2") (pin "2") (pinfunction "2_2") (pintype "passive"))
      (node (ref "C3") (pin "2") (pinfunction "2_2") (pintype "passive"))
      (node (ref "C4") (pin "2") (pinfunction "2_2") (pintype "passive"))
      (node (ref "C5") (pin "2") (pinfunction "2_2") (pintype "passive"))
      (node (ref "C6") (pin "2") (pinfunction "2_2") (pintype "passive"))
      (node (ref "C9") (pin "1") (pinfunction "1_1") (pintype "passive"))
      (node (ref "D34") (pin "C") (pinfunction "C_C") (pintype "passive"))
      (node (ref "IC1") (pin "5") (pinfunction "VCC_5") (pintype "power_in"))
      (node (ref "JP1") (pin "2") (pinfunction "2_2") (pintype "passive"))
      (node (ref "JP2") (pin "2") (pinfunction "2_2") (pintype "passive"))
      (node (ref "JP3") (pin "2") (pinfunction "2_2") (pintype "passive"))
      (node (ref "JP4") (pin "2") (pinfunction "2_2") (pintype "passive"))
      (node (ref "LED1") (pin "2") (pinfunction "VDD_2") (pintype "power_in"))
      (node (ref "LED10") (pin "2") (pinfunction "VDD_2") (pintype "power_in"))
      (node (ref "LED11") (pin "2") (pinfunction "VDD_2") (pintype "power_in"))
      (node (ref "LED12") (pin "2") (pinfunction "VDD_2") (pintype "power_in"))
      (node (ref "LED13") (pin "2") (pinfunction "VDD_2") (pintype "power_in"))
      (node (ref "LED14") (pin "2") (pinfunction "VDD_2") (pintype "power_in"))
      (node (ref "LED15") (pin "2") (pinfunction "VDD_2") (pintype "power_in"))
      (node (ref "LED16") (pin "2") (pinfunction "VDD_2") (pintype "power_in"))
      (node (ref "LED17") (pin "2") (pinfunction "VDD_2") (pintype "power_in"))
      (node (ref "LED18") (pin "2") (pinfunction "VDD_2") (pintype "power_in"))
      (node (ref "LED19") (pin "2") (pinfunction "VDD_2") (pintype "power_in"))
      (node (ref "LED2") (pin "2") (pinfunction "VDD_2") (pintype "power_in"))
      (node (ref "LED20") (pin "2") (pinfunction "VDD_2") (pintype "power_in"))
      (node (ref "LED21") (pin "2") (pinfunction "VDD_2") (pintype "power_in"))
      (node (ref "LED22") (pin "2") (pinfunction "VDD_2") (pintype "power_in"))
      (node (ref "LED23") (pin "2") (pinfunction "VDD_2") (pintype "power_in"))
      (node (ref "LED24") (pin "2") (pinfunction "VDD_2") (pintype "power_in"))
      (node (ref "LED25") (pin "2") (pinfunction "VDD_2") (pintype "power_in"))
      (node (ref "LED26") (pin "2") (pinfunction "VDD_2") (pintype "power_in"))
      (node (ref "LED27") (pin "2") (pinfunction "VDD_2") (pintype "power_in"))
      (node (ref "LED28") (pin "2") (pinfunction "VDD_2") (pintype "power_in"))
      (node (ref "LED29") (pin "2") (pinfunction "VDD_2") (pintype "power_in"))
      (node (ref "LED3") (pin "2") (pinfunction "VDD_2") (pintype "power_in"))
      (node (ref "LED30") (pin "2") (pinfunction "VDD_2") (pintype "power_in"))
      (node (ref "LED31") (pin "2") (pinfunction "VDD_2") (pintype "power_in"))
      (node (ref "LED32") (pin "2") (pinfunction "VDD_2") (pintype "power_in"))
      (node (ref "LED4") (pin "2") (pinfunction "VDD_2") (pintype "power_in"))
      (node (ref "LED5") (pin "2") (pinfunction "VDD_2") (pintype "power_in"))
      (node (ref "LED6") (pin "2") (pinfunction "VDD_2") (pintype "power_in"))
      (node (ref "LED7") (pin "2") (pinfunction "VDD_2") (pintype "power_in"))
      (node (ref "LED8") (pin "2") (pinfunction "VDD_2") (pintype "power_in"))
      (node (ref "LED9") (pin "2") (pinfunction "VDD_2") (pintype "power_in"))
      (node (ref "U1") (pin "1") (pinfunction "IN_1") (pintype "power_in"))
      (node (ref "U1") (pin "3") (pinfunction "EN_3") (pintype "input"))
    )
    (net (code "116") (name "VSS") (class "Default")
      (node (ref "C20") (pin "2") (pinfunction "2_2") (pintype "passive"))
      (node (ref "C21") (pin "2") (pinfunction "2_2") (pintype "passive"))
      (node (ref "C22") (pin "2") (pinfunction "2_2") (pintype "passive"))
      (node (ref "FB4") (pin "2") (pinfunction "P$2_2") (pintype "passive"))
      (node (ref "IC4") (pin "5") (pinfunction "GNDA_5") (pintype "power_in"))
    )
    (net (code "117") (name "VSW") (class "Default")
      (node (ref "IC4") (pin "43") (pinfunction "VSW_43") (pintype "power_in"))
    )
    (net (code "118") (name "unconnected-(IC4A-PA00{slash}EINT0{slash}SERCOM1.0-Pad1)") (class "Default")
      (node (ref "IC4") (pin "1") (pinfunction "PA00/EINT0/SERCOM1.0_1") (pintype "bidirectional"))
    )
    (net (code "119") (name "unconnected-(IC4A-PA01{slash}EINT1{slash}SERCOM1.1-Pad2)") (class "Default")
      (node (ref "IC4") (pin "2") (pinfunction "PA01/EINT1/SERCOM1.1_2") (pintype "bidirectional"))
    )
    (net (code "120") (name "unconnected-(L2-CKO-Pad2)") (class "Default")
      (node (ref "L2") (pin "2") (pinfunction "CKO_2") (pintype "output"))
    )
    (net (code "121") (name "unconnected-(L2-DO-Pad1)") (class "Default")
      (node (ref "L2") (pin "1") (pinfunction "DO_1") (pintype "output"))
    )
    (net (code "122") (name "unconnected-(LED32-DO-Pad3)") (class "Default")
      (node (ref "LED32") (pin "3") (pinfunction "DO_3") (pintype "output"))
    )
    (net (code "123") (name "unconnected-(U1-P4-Pad4)") (class "Default")
      (node (ref "U1") (pin "4") (pinfunction "P4_4") (pintype "bidirectional"))
    )
    (net (code "124") (name "unconnected-(U4-INT1-Pad8)") (class "Default")
      (node (ref "U4") (pin "8") (pinfunction "INT1_8") (pintype "bidirectional"))
    )
    (net (code "125") (name "unconnected-(U4-INT2-Pad9)") (class "Default")
      (node (ref "U4") (pin "9") (pinfunction "INT2_9") (pintype "bidirectional"))
    )
    (net (code "126") (name "unconnected-(U4-NC-Pad10)") (class "Default")
      (node (ref "U4") (pin "10") (pinfunction "NC_10") (pintype "bidirectional"))
    )
    (net (code "127") (name "unconnected-(U4-RSV-Pad3)") (class "Default")
      (node (ref "U4") (pin "3") (pinfunction "RSV_3") (pintype "bidirectional"))
    )
    (net (code "128") (name "unconnected-(U4-RSV-Pad11)") (class "Default")
      (node (ref "U4") (pin "11") (pinfunction "RSV_11") (pintype "bidirectional"))
    )
    (net (code "129") (name "unconnected-(X2-GNDDETECT-Pad9)") (class "Default")
      (node (ref "X2") (pin "9") (pinfunction "GNDDETECT_9") (pintype "bidirectional"))
    )
    (net (code "130") (name "unconnected-(X2-KEY-Pad7)") (class "Default")
      (node (ref "X2") (pin "7") (pinfunction "KEY_7") (pintype "bidirectional"))
    )
    (net (code "131") (name "unconnected-(X2-SWO-Pad6)") (class "Default")
      (node (ref "X2") (pin "6") (pinfunction "SWO_6") (pintype "bidirectional"))
    )
    (net (code "132") (name "unconnected-(X2-TDI-Pad8)") (class "Default")
      (node (ref "X2") (pin "8") (pinfunction "TDI_8") (pintype "bidirectional"))
    )
    (net (code "133") (name "unconnected-(X3-PadID)") (class "Default")
      (node (ref "X3") (pin "ID") (pinfunction "ID_ID") (pintype "bidirectional"))
    )
    (net (code "134") (name "~{RESET}") (class "Default")
      (node (ref "C15") (pin "2") (pinfunction "2_2") (pintype "passive"))
      (node (ref "IC4") (pin "40") (pinfunction "/RESET_40") (pintype "bidirectional"))
      (node (ref "R2") (pin "1") (pinfunction "1_1") (pintype "passive"))
      (node (ref "SW1") (pin "1") (pinfunction "P_1") (pintype "passive"))
      (node (ref "SW1") (pin "3") (pinfunction "P1_3") (pintype "passive"))
      (node (ref "TP7") (pin "P$1") (pinfunction "P$1_P$1") (pintype "bidirectional"))
      (node (ref "X2") (pin "10") (pinfunction "NRESET_10") (pintype "bidirectional"))
    )
  )
)
